# display_driver_rev_A.net
KiCad netlist of a schematic drawn in EAGLE
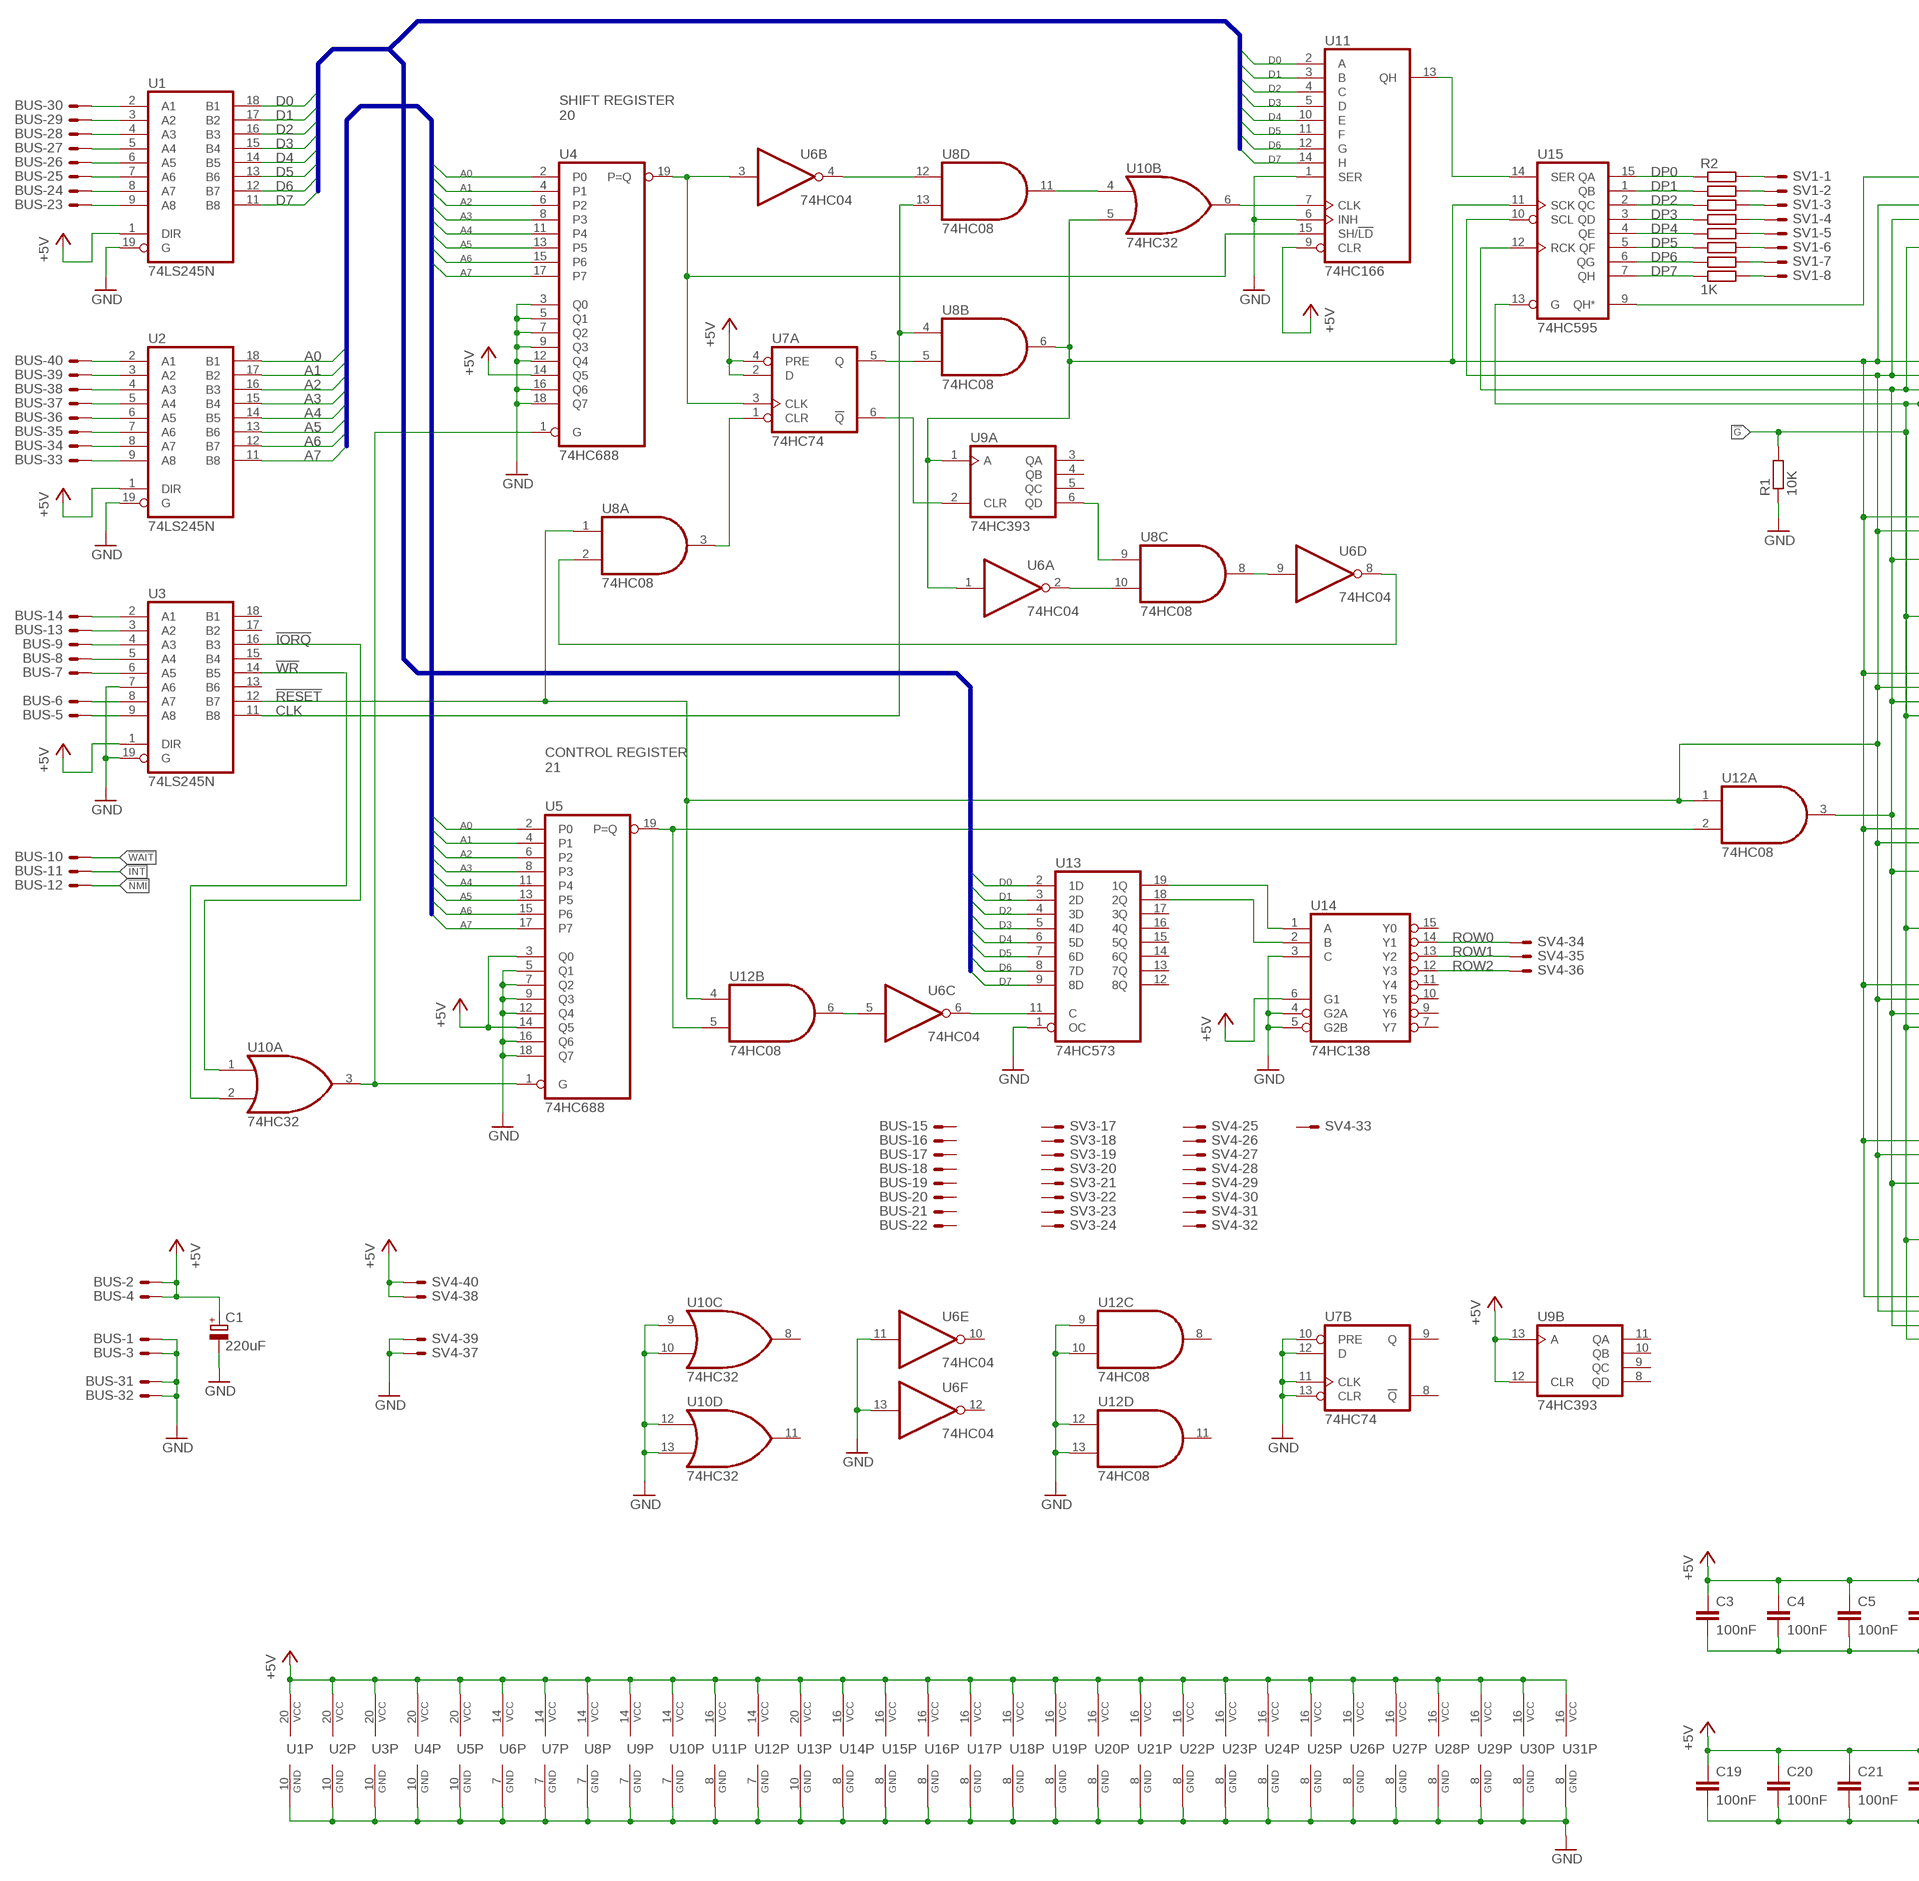
[diagram p0: schematic, sheet 1, part 1 of 2]
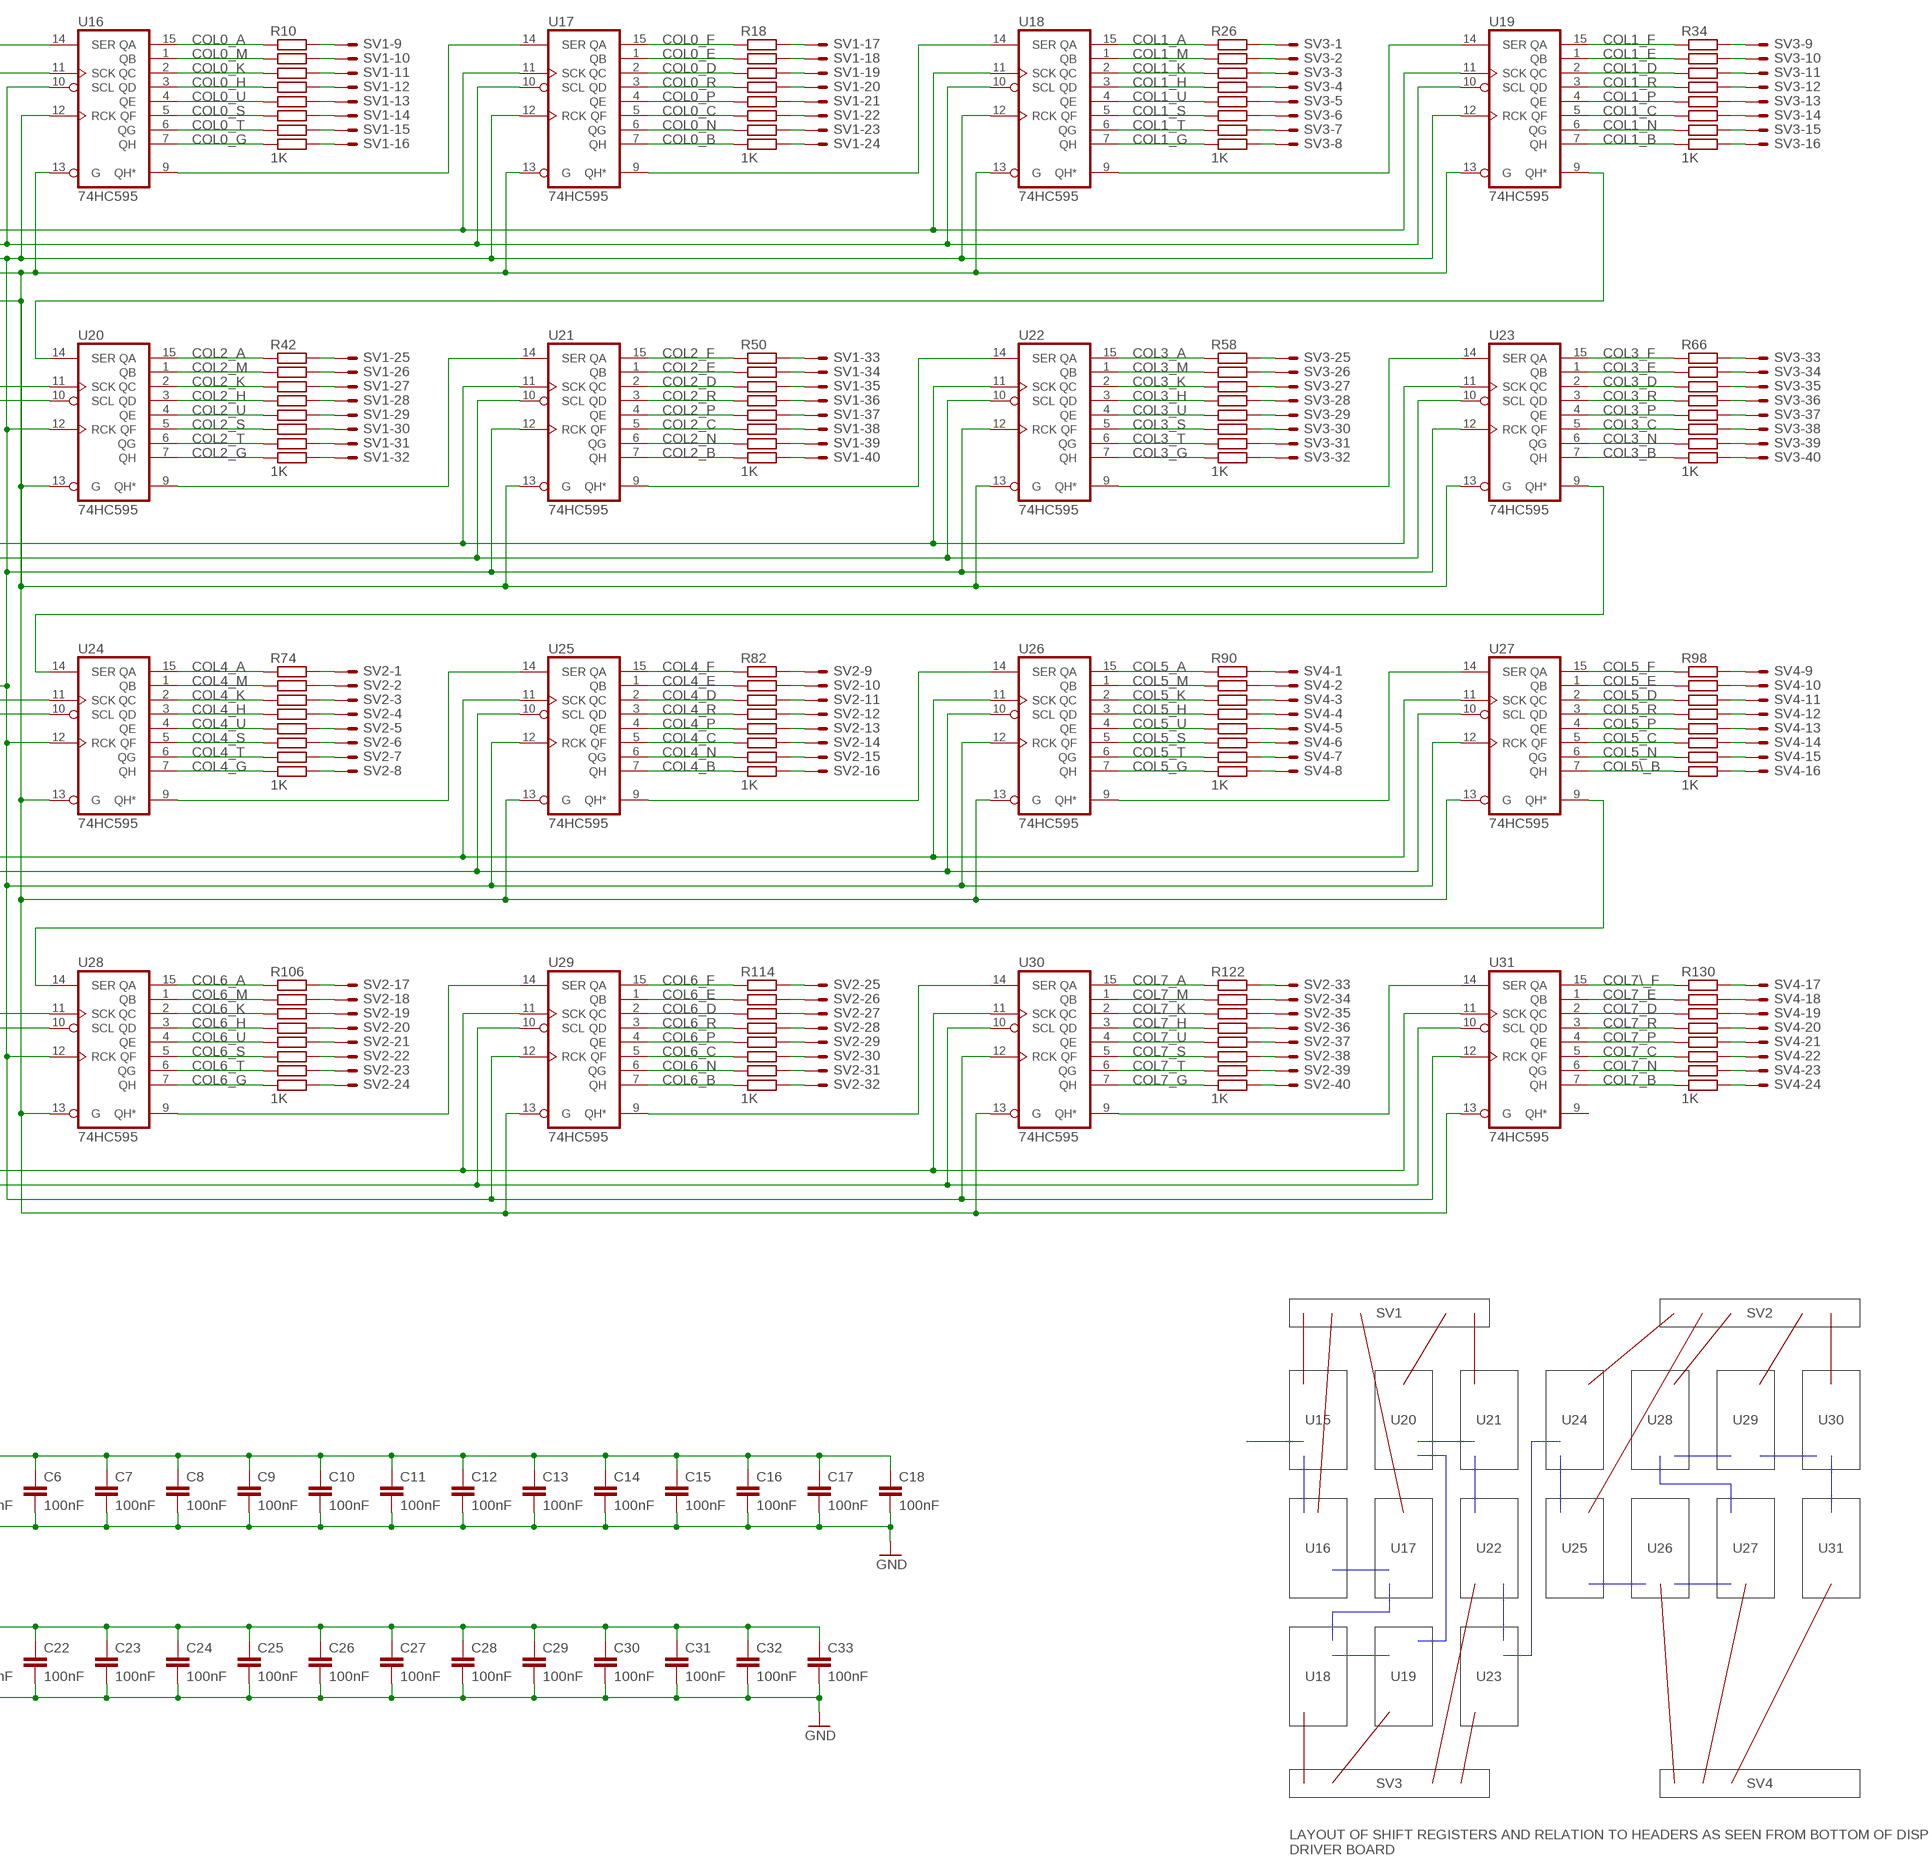
[diagram p1: schematic, sheet 1, part 2 of 2]

(export (version "E")
  (design (tool "Eeschema 10.0.6"))
  (components
    (comp (ref "BUS")
      (value "ML40E")
      (footprint "eagle-import:ML40")
      (libsource (lib "eagle-import") (part "ML40E"))
    )
    (comp (ref "C1")
      (value "220uF")
      (footprint "eagle-import:E3,5-8")
      (libsource (lib "eagle-import") (part "CPOL-EUE3.5-8"))
    )
    (comp (ref "C3")
      (value "100nF")
      (footprint "eagle-import:C050-025X075")
      (libsource (lib "eagle-import") (part "C-EU050-025X075"))
    )
    (comp (ref "C4")
      (value "100nF")
      (footprint "eagle-import:C050-025X075")
      (libsource (lib "eagle-import") (part "C-EU050-025X075"))
    )
    (comp (ref "C5")
      (value "100nF")
      (footprint "eagle-import:C050-025X075")
      (libsource (lib "eagle-import") (part "C-EU050-025X075"))
    )
    (comp (ref "C6")
      (value "100nF")
      (footprint "eagle-import:C050-025X075")
      (libsource (lib "eagle-import") (part "C-EU050-025X075"))
    )
    (comp (ref "C7")
      (value "100nF")
      (footprint "eagle-import:C050-025X075")
      (libsource (lib "eagle-import") (part "C-EU050-025X075"))
    )
    (comp (ref "C8")
      (value "100nF")
      (footprint "eagle-import:C050-025X075")
      (libsource (lib "eagle-import") (part "C-EU050-025X075"))
    )
    (comp (ref "C9")
      (value "100nF")
      (footprint "eagle-import:C050-025X075")
      (libsource (lib "eagle-import") (part "C-EU050-025X075"))
    )
    (comp (ref "C10")
      (value "100nF")
      (footprint "eagle-import:C050-025X075")
      (libsource (lib "eagle-import") (part "C-EU050-025X075"))
    )
    (comp (ref "C11")
      (value "100nF")
      (footprint "eagle-import:C050-025X075")
      (libsource (lib "eagle-import") (part "C-EU050-025X075"))
    )
    (comp (ref "C12")
      (value "100nF")
      (footprint "eagle-import:C050-025X075")
      (libsource (lib "eagle-import") (part "C-EU050-025X075"))
    )
    (comp (ref "C13")
      (value "100nF")
      (footprint "eagle-import:C050-025X075")
      (libsource (lib "eagle-import") (part "C-EU050-025X075"))
    )
    (comp (ref "C14")
      (value "100nF")
      (footprint "eagle-import:C050-025X075")
      (libsource (lib "eagle-import") (part "C-EU050-025X075"))
    )
    (comp (ref "C15")
      (value "100nF")
      (footprint "eagle-import:C050-025X075")
      (libsource (lib "eagle-import") (part "C-EU050-025X075"))
    )
    (comp (ref "C16")
      (value "100nF")
      (footprint "eagle-import:C050-025X075")
      (libsource (lib "eagle-import") (part "C-EU050-025X075"))
    )
    (comp (ref "C17")
      (value "100nF")
      (footprint "eagle-import:C050-025X075")
      (libsource (lib "eagle-import") (part "C-EU050-025X075"))
    )
    (comp (ref "C18")
      (value "100nF")
      (footprint "eagle-import:C050-025X075")
      (libsource (lib "eagle-import") (part "C-EU050-025X075"))
    )
    (comp (ref "C19")
      (value "100nF")
      (footprint "eagle-import:C050-025X075")
      (libsource (lib "eagle-import") (part "C-EU050-025X075"))
    )
    (comp (ref "C20")
      (value "100nF")
      (footprint "eagle-import:C050-025X075")
      (libsource (lib "eagle-import") (part "C-EU050-025X075"))
    )
    (comp (ref "C21")
      (value "100nF")
      (footprint "eagle-import:C050-025X075")
      (libsource (lib "eagle-import") (part "C-EU050-025X075"))
    )
    (comp (ref "C22")
      (value "100nF")
      (footprint "eagle-import:C050-025X075")
      (libsource (lib "eagle-import") (part "C-EU050-025X075"))
    )
    (comp (ref "C23")
      (value "100nF")
      (footprint "eagle-import:C050-025X075")
      (libsource (lib "eagle-import") (part "C-EU050-025X075"))
    )
    (comp (ref "C24")
      (value "100nF")
      (footprint "eagle-import:C050-025X075")
      (libsource (lib "eagle-import") (part "C-EU050-025X075"))
    )
    (comp (ref "C25")
      (value "100nF")
      (footprint "eagle-import:C050-025X075")
      (libsource (lib "eagle-import") (part "C-EU050-025X075"))
    )
    (comp (ref "C26")
      (value "100nF")
      (footprint "eagle-import:C050-025X075")
      (libsource (lib "eagle-import") (part "C-EU050-025X075"))
    )
    (comp (ref "C27")
      (value "100nF")
      (footprint "eagle-import:C050-025X075")
      (libsource (lib "eagle-import") (part "C-EU050-025X075"))
    )
    (comp (ref "C28")
      (value "100nF")
      (footprint "eagle-import:C050-025X075")
      (libsource (lib "eagle-import") (part "C-EU050-025X075"))
    )
    (comp (ref "C29")
      (value "100nF")
      (footprint "eagle-import:C050-025X075")
      (libsource (lib "eagle-import") (part "C-EU050-025X075"))
    )
    (comp (ref "C30")
      (value "100nF")
      (footprint "eagle-import:C050-025X075")
      (libsource (lib "eagle-import") (part "C-EU050-025X075"))
    )
    (comp (ref "C31")
      (value "100nF")
      (footprint "eagle-import:C050-025X075")
      (libsource (lib "eagle-import") (part "C-EU050-025X075"))
    )
    (comp (ref "C32")
      (value "100nF")
      (footprint "eagle-import:C050-025X075")
      (libsource (lib "eagle-import") (part "C-EU050-025X075"))
    )
    (comp (ref "C33")
      (value "100nF")
      (footprint "eagle-import:C050-025X075")
      (libsource (lib "eagle-import") (part "C-EU050-025X075"))
    )
    (comp (ref "R1")
      (value "10K")
      (footprint "eagle-import:0207_10")
      (libsource (lib "eagle-import") (part "R-EU_0207/10"))
    )
    (comp (ref "R2")
      (value "1K")
      (footprint "eagle-import:0207_10")
      (libsource (lib "eagle-import") (part "R-EU_0207/10"))
    )
    (comp (ref "R3")
      (value "1K")
      (footprint "eagle-import:0207_10")
      (libsource (lib "eagle-import") (part "R-EU_0207/10"))
    )
    (comp (ref "R4")
      (value "1K")
      (footprint "eagle-import:0207_10")
      (libsource (lib "eagle-import") (part "R-EU_0207/10"))
    )
    (comp (ref "R5")
      (value "1K")
      (footprint "eagle-import:0207_10")
      (libsource (lib "eagle-import") (part "R-EU_0207/10"))
    )
    (comp (ref "R6")
      (value "1K")
      (footprint "eagle-import:0207_10")
      (libsource (lib "eagle-import") (part "R-EU_0207/10"))
    )
    (comp (ref "R7")
      (value "1K")
      (footprint "eagle-import:0207_10")
      (libsource (lib "eagle-import") (part "R-EU_0207/10"))
    )
    (comp (ref "R8")
      (value "1K")
      (footprint "eagle-import:0207_10")
      (libsource (lib "eagle-import") (part "R-EU_0207/10"))
    )
    (comp (ref "R9")
      (value "1K")
      (footprint "eagle-import:0207_10")
      (libsource (lib "eagle-import") (part "R-EU_0207/10"))
    )
    (comp (ref "R10")
      (value "1K")
      (footprint "eagle-import:0207_10")
      (libsource (lib "eagle-import") (part "R-EU_0207/10"))
    )
    (comp (ref "R11")
      (value "1K")
      (footprint "eagle-import:0207_10")
      (libsource (lib "eagle-import") (part "R-EU_0207/10"))
    )
    (comp (ref "R12")
      (value "1K")
      (footprint "eagle-import:0207_10")
      (libsource (lib "eagle-import") (part "R-EU_0207/10"))
    )
    (comp (ref "R13")
      (value "1K")
      (footprint "eagle-import:0207_10")
      (libsource (lib "eagle-import") (part "R-EU_0207/10"))
    )
    (comp (ref "R14")
      (value "1K")
      (footprint "eagle-import:0207_10")
      (libsource (lib "eagle-import") (part "R-EU_0207/10"))
    )
    (comp (ref "R15")
      (value "1K")
      (footprint "eagle-import:0207_10")
      (libsource (lib "eagle-import") (part "R-EU_0207/10"))
    )
    (comp (ref "R16")
      (value "1K")
      (footprint "eagle-import:0207_10")
      (libsource (lib "eagle-import") (part "R-EU_0207/10"))
    )
    (comp (ref "R17")
      (value "1K")
      (footprint "eagle-import:0207_10")
      (libsource (lib "eagle-import") (part "R-EU_0207/10"))
    )
    (comp (ref "R18")
      (value "1K")
      (footprint "eagle-import:0207_10")
      (libsource (lib "eagle-import") (part "R-EU_0207/10"))
    )
    (comp (ref "R19")
      (value "1K")
      (footprint "eagle-import:0207_10")
      (libsource (lib "eagle-import") (part "R-EU_0207/10"))
    )
    (comp (ref "R20")
      (value "1K")
      (footprint "eagle-import:0207_10")
      (libsource (lib "eagle-import") (part "R-EU_0207/10"))
    )
    (comp (ref "R21")
      (value "1K")
      (footprint "eagle-import:0207_10")
      (libsource (lib "eagle-import") (part "R-EU_0207/10"))
    )
    (comp (ref "R22")
      (value "1K")
      (footprint "eagle-import:0207_10")
      (libsource (lib "eagle-import") (part "R-EU_0207/10"))
    )
    (comp (ref "R23")
      (value "1K")
      (footprint "eagle-import:0207_10")
      (libsource (lib "eagle-import") (part "R-EU_0207/10"))
    )
    (comp (ref "R24")
      (value "1K")
      (footprint "eagle-import:0207_10")
      (libsource (lib "eagle-import") (part "R-EU_0207/10"))
    )
    (comp (ref "R25")
      (value "1K")
      (footprint "eagle-import:0207_10")
      (libsource (lib "eagle-import") (part "R-EU_0207/10"))
    )
    (comp (ref "R26")
      (value "1K")
      (footprint "eagle-import:0207_10")
      (libsource (lib "eagle-import") (part "R-EU_0207/10"))
    )
    (comp (ref "R27")
      (value "1K")
      (footprint "eagle-import:0207_10")
      (libsource (lib "eagle-import") (part "R-EU_0207/10"))
    )
    (comp (ref "R28")
      (value "1K")
      (footprint "eagle-import:0207_10")
      (libsource (lib "eagle-import") (part "R-EU_0207/10"))
    )
    (comp (ref "R29")
      (value "1K")
      (footprint "eagle-import:0207_10")
      (libsource (lib "eagle-import") (part "R-EU_0207/10"))
    )
    (comp (ref "R30")
      (value "1K")
      (footprint "eagle-import:0207_10")
      (libsource (lib "eagle-import") (part "R-EU_0207/10"))
    )
    (comp (ref "R31")
      (value "1K")
      (footprint "eagle-import:0207_10")
      (libsource (lib "eagle-import") (part "R-EU_0207/10"))
    )
    (comp (ref "R32")
      (value "1K")
      (footprint "eagle-import:0207_10")
      (libsource (lib "eagle-import") (part "R-EU_0207/10"))
    )
    (comp (ref "R33")
      (value "1K")
      (footprint "eagle-import:0207_10")
      (libsource (lib "eagle-import") (part "R-EU_0207/10"))
    )
    (comp (ref "R34")
      (value "1K")
      (footprint "eagle-import:0207_10")
      (libsource (lib "eagle-import") (part "R-EU_0207/10"))
    )
    (comp (ref "R35")
      (value "1K")
      (footprint "eagle-import:0207_10")
      (libsource (lib "eagle-import") (part "R-EU_0207/10"))
    )
    (comp (ref "R36")
      (value "1K")
      (footprint "eagle-import:0207_10")
      (libsource (lib "eagle-import") (part "R-EU_0207/10"))
    )
    (comp (ref "R37")
      (value "1K")
      (footprint "eagle-import:0207_10")
      (libsource (lib "eagle-import") (part "R-EU_0207/10"))
    )
    (comp (ref "R38")
      (value "1K")
      (footprint "eagle-import:0207_10")
      (libsource (lib "eagle-import") (part "R-EU_0207/10"))
    )
    (comp (ref "R39")
      (value "1K")
      (footprint "eagle-import:0207_10")
      (libsource (lib "eagle-import") (part "R-EU_0207/10"))
    )
    (comp (ref "R40")
      (value "1K")
      (footprint "eagle-import:0207_10")
      (libsource (lib "eagle-import") (part "R-EU_0207/10"))
    )
    (comp (ref "R41")
      (value "1K")
      (footprint "eagle-import:0207_10")
      (libsource (lib "eagle-import") (part "R-EU_0207/10"))
    )
    (comp (ref "R42")
      (value "1K")
      (footprint "eagle-import:0207_10")
      (libsource (lib "eagle-import") (part "R-EU_0207/10"))
    )
    (comp (ref "R43")
      (value "1K")
      (footprint "eagle-import:0207_10")
      (libsource (lib "eagle-import") (part "R-EU_0207/10"))
    )
    (comp (ref "R44")
      (value "1K")
      (footprint "eagle-import:0207_10")
      (libsource (lib "eagle-import") (part "R-EU_0207/10"))
    )
    (comp (ref "R45")
      (value "1K")
      (footprint "eagle-import:0207_10")
      (libsource (lib "eagle-import") (part "R-EU_0207/10"))
    )
    (comp (ref "R46")
      (value "1K")
      (footprint "eagle-import:0207_10")
      (libsource (lib "eagle-import") (part "R-EU_0207/10"))
    )
    (comp (ref "R47")
      (value "1K")
      (footprint "eagle-import:0207_10")
      (libsource (lib "eagle-import") (part "R-EU_0207/10"))
    )
    (comp (ref "R48")
      (value "1K")
      (footprint "eagle-import:0207_10")
      (libsource (lib "eagle-import") (part "R-EU_0207/10"))
    )
    (comp (ref "R49")
      (value "1K")
      (footprint "eagle-import:0207_10")
      (libsource (lib "eagle-import") (part "R-EU_0207/10"))
    )
    (comp (ref "R50")
      (value "1K")
      (footprint "eagle-import:0207_10")
      (libsource (lib "eagle-import") (part "R-EU_0207/10"))
    )
    (comp (ref "R51")
      (value "1K")
      (footprint "eagle-import:0207_10")
      (libsource (lib "eagle-import") (part "R-EU_0207/10"))
    )
    (comp (ref "R52")
      (value "1K")
      (footprint "eagle-import:0207_10")
      (libsource (lib "eagle-import") (part "R-EU_0207/10"))
    )
    (comp (ref "R53")
      (value "1K")
      (footprint "eagle-import:0207_10")
      (libsource (lib "eagle-import") (part "R-EU_0207/10"))
    )
    (comp (ref "R54")
      (value "1K")
      (footprint "eagle-import:0207_10")
      (libsource (lib "eagle-import") (part "R-EU_0207/10"))
    )
    (comp (ref "R55")
      (value "1K")
      (footprint "eagle-import:0207_10")
      (libsource (lib "eagle-import") (part "R-EU_0207/10"))
    )
    (comp (ref "R56")
      (value "1K")
      (footprint "eagle-import:0207_10")
      (libsource (lib "eagle-import") (part "R-EU_0207/10"))
    )
    (comp (ref "R57")
      (value "1K")
      (footprint "eagle-import:0207_10")
      (libsource (lib "eagle-import") (part "R-EU_0207/10"))
    )
    (comp (ref "R58")
      (value "1K")
      (footprint "eagle-import:0207_10")
      (libsource (lib "eagle-import") (part "R-EU_0207/10"))
    )
    (comp (ref "R59")
      (value "1K")
      (footprint "eagle-import:0207_10")
      (libsource (lib "eagle-import") (part "R-EU_0207/10"))
    )
    (comp (ref "R60")
      (value "1K")
      (footprint "eagle-import:0207_10")
      (libsource (lib "eagle-import") (part "R-EU_0207/10"))
    )
    (comp (ref "R61")
      (value "1K")
      (footprint "eagle-import:0207_10")
      (libsource (lib "eagle-import") (part "R-EU_0207/10"))
    )
    (comp (ref "R62")
      (value "1K")
      (footprint "eagle-import:0207_10")
      (libsource (lib "eagle-import") (part "R-EU_0207/10"))
    )
    (comp (ref "R63")
      (value "1K")
      (footprint "eagle-import:0207_10")
      (libsource (lib "eagle-import") (part "R-EU_0207/10"))
    )
    (comp (ref "R64")
      (value "1K")
      (footprint "eagle-import:0207_10")
      (libsource (lib "eagle-import") (part "R-EU_0207/10"))
    )
    (comp (ref "R65")
      (value "1K")
      (footprint "eagle-import:0207_10")
      (libsource (lib "eagle-import") (part "R-EU_0207/10"))
    )
    (comp (ref "R66")
      (value "1K")
      (footprint "eagle-import:0207_10")
      (libsource (lib "eagle-import") (part "R-EU_0207/10"))
    )
    (comp (ref "R67")
      (value "1K")
      (footprint "eagle-import:0207_10")
      (libsource (lib "eagle-import") (part "R-EU_0207/10"))
    )
    (comp (ref "R68")
      (value "1K")
      (footprint "eagle-import:0207_10")
      (libsource (lib "eagle-import") (part "R-EU_0207/10"))
    )
    (comp (ref "R69")
      (value "1K")
      (footprint "eagle-import:0207_10")
      (libsource (lib "eagle-import") (part "R-EU_0207/10"))
    )
    (comp (ref "R70")
      (value "1K")
      (footprint "eagle-import:0207_10")
      (libsource (lib "eagle-import") (part "R-EU_0207/10"))
    )
    (comp (ref "R71")
      (value "1K")
      (footprint "eagle-import:0207_10")
      (libsource (lib "eagle-import") (part "R-EU_0207/10"))
    )
    (comp (ref "R72")
      (value "1K")
      (footprint "eagle-import:0207_10")
      (libsource (lib "eagle-import") (part "R-EU_0207/10"))
    )
    (comp (ref "R73")
      (value "1K")
      (footprint "eagle-import:0207_10")
      (libsource (lib "eagle-import") (part "R-EU_0207/10"))
    )
    (comp (ref "R74")
      (value "1K")
      (footprint "eagle-import:0207_10")
      (libsource (lib "eagle-import") (part "R-EU_0207/10"))
    )
    (comp (ref "R75")
      (value "1K")
      (footprint "eagle-import:0207_10")
      (libsource (lib "eagle-import") (part "R-EU_0207/10"))
    )
    (comp (ref "R76")
      (value "1K")
      (footprint "eagle-import:0207_10")
      (libsource (lib "eagle-import") (part "R-EU_0207/10"))
    )
    (comp (ref "R77")
      (value "1K")
      (footprint "eagle-import:0207_10")
      (libsource (lib "eagle-import") (part "R-EU_0207/10"))
    )
    (comp (ref "R78")
      (value "1K")
      (footprint "eagle-import:0207_10")
      (libsource (lib "eagle-import") (part "R-EU_0207/10"))
    )
    (comp (ref "R79")
      (value "1K")
      (footprint "eagle-import:0207_10")
      (libsource (lib "eagle-import") (part "R-EU_0207/10"))
    )
    (comp (ref "R80")
      (value "1K")
      (footprint "eagle-import:0207_10")
      (libsource (lib "eagle-import") (part "R-EU_0207/10"))
    )
    (comp (ref "R81")
      (value "1K")
      (footprint "eagle-import:0207_10")
      (libsource (lib "eagle-import") (part "R-EU_0207/10"))
    )
    (comp (ref "R82")
      (value "1K")
      (footprint "eagle-import:0207_10")
      (libsource (lib "eagle-import") (part "R-EU_0207/10"))
    )
    (comp (ref "R83")
      (value "1K")
      (footprint "eagle-import:0207_10")
      (libsource (lib "eagle-import") (part "R-EU_0207/10"))
    )
    (comp (ref "R84")
      (value "1K")
      (footprint "eagle-import:0207_10")
      (libsource (lib "eagle-import") (part "R-EU_0207/10"))
    )
    (comp (ref "R85")
      (value "1K")
      (footprint "eagle-import:0207_10")
      (libsource (lib "eagle-import") (part "R-EU_0207/10"))
    )
    (comp (ref "R86")
      (value "1K")
      (footprint "eagle-import:0207_10")
      (libsource (lib "eagle-import") (part "R-EU_0207/10"))
    )
    (comp (ref "R87")
      (value "1K")
      (footprint "eagle-import:0207_10")
      (libsource (lib "eagle-import") (part "R-EU_0207/10"))
    )
    (comp (ref "R88")
      (value "1K")
      (footprint "eagle-import:0207_10")
      (libsource (lib "eagle-import") (part "R-EU_0207/10"))
    )
    (comp (ref "R89")
      (value "1K")
      (footprint "eagle-import:0207_10")
      (libsource (lib "eagle-import") (part "R-EU_0207/10"))
    )
    (comp (ref "R90")
      (value "1K")
      (footprint "eagle-import:0207_10")
      (libsource (lib "eagle-import") (part "R-EU_0207/10"))
    )
    (comp (ref "R91")
      (value "1K")
      (footprint "eagle-import:0207_10")
      (libsource (lib "eagle-import") (part "R-EU_0207/10"))
    )
    (comp (ref "R92")
      (value "1K")
      (footprint "eagle-import:0207_10")
      (libsource (lib "eagle-import") (part "R-EU_0207/10"))
    )
    (comp (ref "R93")
      (value "1K")
      (footprint "eagle-import:0207_10")
      (libsource (lib "eagle-import") (part "R-EU_0207/10"))
    )
    (comp (ref "R94")
      (value "1K")
      (footprint "eagle-import:0207_10")
      (libsource (lib "eagle-import") (part "R-EU_0207/10"))
    )
    (comp (ref "R95")
      (value "1K")
      (footprint "eagle-import:0207_10")
      (libsource (lib "eagle-import") (part "R-EU_0207/10"))
    )
    (comp (ref "R96")
      (value "1K")
      (footprint "eagle-import:0207_10")
      (libsource (lib "eagle-import") (part "R-EU_0207/10"))
    )
    (comp (ref "R97")
      (value "1K")
      (footprint "eagle-import:0207_10")
      (libsource (lib "eagle-import") (part "R-EU_0207/10"))
    )
    (comp (ref "R98")
      (value "1K")
      (footprint "eagle-import:0207_10")
      (libsource (lib "eagle-import") (part "R-EU_0207/10"))
    )
    (comp (ref "R99")
      (value "1K")
      (footprint "eagle-import:0207_10")
      (libsource (lib "eagle-import") (part "R-EU_0207/10"))
    )
    (comp (ref "R100")
      (value "1K")
      (footprint "eagle-import:0207_10")
      (libsource (lib "eagle-import") (part "R-EU_0207/10"))
    )
    (comp (ref "R101")
      (value "1K")
      (footprint "eagle-import:0207_10")
      (libsource (lib "eagle-import") (part "R-EU_0207/10"))
    )
    (comp (ref "R102")
      (value "1K")
      (footprint "eagle-import:0207_10")
      (libsource (lib "eagle-import") (part "R-EU_0207/10"))
    )
    (comp (ref "R103")
      (value "1K")
      (footprint "eagle-import:0207_10")
      (libsource (lib "eagle-import") (part "R-EU_0207/10"))
    )
    (comp (ref "R104")
      (value "1K")
      (footprint "eagle-import:0207_10")
      (libsource (lib "eagle-import") (part "R-EU_0207/10"))
    )
    (comp (ref "R105")
      (value "1K")
      (footprint "eagle-import:0207_10")
      (libsource (lib "eagle-import") (part "R-EU_0207/10"))
    )
    (comp (ref "R106")
      (value "1K")
      (footprint "eagle-import:0207_10")
      (libsource (lib "eagle-import") (part "R-EU_0207/10"))
    )
    (comp (ref "R107")
      (value "1K")
      (footprint "eagle-import:0207_10")
      (libsource (lib "eagle-import") (part "R-EU_0207/10"))
    )
    (comp (ref "R108")
      (value "1K")
      (footprint "eagle-import:0207_10")
      (libsource (lib "eagle-import") (part "R-EU_0207/10"))
    )
    (comp (ref "R109")
      (value "1K")
      (footprint "eagle-import:0207_10")
      (libsource (lib "eagle-import") (part "R-EU_0207/10"))
    )
    (comp (ref "R110")
      (value "1K")
      (footprint "eagle-import:0207_10")
      (libsource (lib "eagle-import") (part "R-EU_0207/10"))
    )
    (comp (ref "R111")
      (value "1K")
      (footprint "eagle-import:0207_10")
      (libsource (lib "eagle-import") (part "R-EU_0207/10"))
    )
    (comp (ref "R112")
      (value "1K")
      (footprint "eagle-import:0207_10")
      (libsource (lib "eagle-import") (part "R-EU_0207/10"))
    )
    (comp (ref "R113")
      (value "1K")
      (footprint "eagle-import:0207_10")
      (libsource (lib "eagle-import") (part "R-EU_0207/10"))
    )
    (comp (ref "R114")
      (value "1K")
      (footprint "eagle-import:0207_10")
      (libsource (lib "eagle-import") (part "R-EU_0207/10"))
    )
    (comp (ref "R115")
      (value "1K")
      (footprint "eagle-import:0207_10")
      (libsource (lib "eagle-import") (part "R-EU_0207/10"))
    )
    (comp (ref "R116")
      (value "1K")
      (footprint "eagle-import:0207_10")
      (libsource (lib "eagle-import") (part "R-EU_0207/10"))
    )
    (comp (ref "R117")
      (value "1K")
      (footprint "eagle-import:0207_10")
      (libsource (lib "eagle-import") (part "R-EU_0207/10"))
    )
    (comp (ref "R118")
      (value "1K")
      (footprint "eagle-import:0207_10")
      (libsource (lib "eagle-import") (part "R-EU_0207/10"))
    )
    (comp (ref "R119")
      (value "1K")
      (footprint "eagle-import:0207_10")
      (libsource (lib "eagle-import") (part "R-EU_0207/10"))
    )
    (comp (ref "R120")
      (value "1K")
      (footprint "eagle-import:0207_10")
      (libsource (lib "eagle-import") (part "R-EU_0207/10"))
    )
    (comp (ref "R121")
      (value "1K")
      (footprint "eagle-import:0207_10")
      (libsource (lib "eagle-import") (part "R-EU_0207/10"))
    )
    (comp (ref "R122")
      (value "1K")
      (footprint "eagle-import:0207_10")
      (libsource (lib "eagle-import") (part "R-EU_0207/10"))
    )
    (comp (ref "R123")
      (value "1K")
      (footprint "eagle-import:0207_10")
      (libsource (lib "eagle-import") (part "R-EU_0207/10"))
    )
    (comp (ref "R124")
      (value "1K")
      (footprint "eagle-import:0207_10")
      (libsource (lib "eagle-import") (part "R-EU_0207/10"))
    )
    (comp (ref "R125")
      (value "1K")
      (footprint "eagle-import:0207_10")
      (libsource (lib "eagle-import") (part "R-EU_0207/10"))
    )
    (comp (ref "R126")
      (value "1K")
      (footprint "eagle-import:0207_10")
      (libsource (lib "eagle-import") (part "R-EU_0207/10"))
    )
    (comp (ref "R127")
      (value "1K")
      (footprint "eagle-import:0207_10")
      (libsource (lib "eagle-import") (part "R-EU_0207/10"))
    )
    (comp (ref "R128")
      (value "1K")
      (footprint "eagle-import:0207_10")
      (libsource (lib "eagle-import") (part "R-EU_0207/10"))
    )
    (comp (ref "R129")
      (value "1K")
      (footprint "eagle-import:0207_10")
      (libsource (lib "eagle-import") (part "R-EU_0207/10"))
    )
    (comp (ref "R130")
      (value "1K")
      (footprint "eagle-import:0207_10")
      (libsource (lib "eagle-import") (part "R-EU_0207/10"))
    )
    (comp (ref "R131")
      (value "1K")
      (footprint "eagle-import:0207_10")
      (libsource (lib "eagle-import") (part "R-EU_0207/10"))
    )
    (comp (ref "R132")
      (value "1K")
      (footprint "eagle-import:0207_10")
      (libsource (lib "eagle-import") (part "R-EU_0207/10"))
    )
    (comp (ref "R133")
      (value "1K")
      (footprint "eagle-import:0207_10")
      (libsource (lib "eagle-import") (part "R-EU_0207/10"))
    )
    (comp (ref "R134")
      (value "1K")
      (footprint "eagle-import:0207_10")
      (libsource (lib "eagle-import") (part "R-EU_0207/10"))
    )
    (comp (ref "R135")
      (value "1K")
      (footprint "eagle-import:0207_10")
      (libsource (lib "eagle-import") (part "R-EU_0207/10"))
    )
    (comp (ref "R136")
      (value "1K")
      (footprint "eagle-import:0207_10")
      (libsource (lib "eagle-import") (part "R-EU_0207/10"))
    )
    (comp (ref "R137")
      (value "1K")
      (footprint "eagle-import:0207_10")
      (libsource (lib "eagle-import") (part "R-EU_0207/10"))
    )
    (comp (ref "SV1")
      (value "ML40E")
      (footprint "eagle-import:ML40")
      (libsource (lib "eagle-import") (part "ML40E"))
    )
    (comp (ref "SV2")
      (value "ML40E")
      (footprint "eagle-import:ML40")
      (libsource (lib "eagle-import") (part "ML40E"))
    )
    (comp (ref "SV3")
      (value "ML40E")
      (footprint "eagle-import:ML40")
      (libsource (lib "eagle-import") (part "ML40E"))
    )
    (comp (ref "SV4")
      (value "ML40E")
      (footprint "eagle-import:ML40")
      (libsource (lib "eagle-import") (part "ML40E"))
    )
    (comp (ref "U1")
      (value "74LS245N")
      (footprint "eagle-import:DIL20")
      (libsource (lib "eagle-import") (part "74245NLS"))
    )
    (comp (ref "U2")
      (value "74LS245N")
      (footprint "eagle-import:DIL20")
      (libsource (lib "eagle-import") (part "74245NLS"))
    )
    (comp (ref "U3")
      (value "74LS245N")
      (footprint "eagle-import:DIL20")
      (libsource (lib "eagle-import") (part "74245NLS"))
    )
    (comp (ref "U4")
      (value "74HC688")
      (footprint "eagle-import:DIL20")
      (libsource (lib "eagle-import") (part "74688NLS"))
    )
    (comp (ref "U5")
      (value "74HC688")
      (footprint "eagle-import:DIL20")
      (libsource (lib "eagle-import") (part "74688NLS"))
    )
    (comp (ref "U6")
      (value "74HC04")
      (footprint "eagle-import:DIL14")
      (libsource (lib "eagle-import") (part "7404NLS"))
    )
    (comp (ref "U7")
      (value "74HC74")
      (footprint "eagle-import:DIL14")
      (libsource (lib "eagle-import") (part "7474NLS"))
    )
    (comp (ref "U8")
      (value "74HC08")
      (footprint "eagle-import:DIL14")
      (libsource (lib "eagle-import") (part "7408NLS"))
    )
    (comp (ref "U9")
      (value "74HC393")
      (footprint "eagle-import:DIL14")
      (libsource (lib "eagle-import") (part "74393NLS"))
    )
    (comp (ref "U10")
      (value "74HC32")
      (footprint "eagle-import:DIL14")
      (libsource (lib "eagle-import") (part "7432NLS"))
    )
    (comp (ref "U11")
      (value "74HC166")
      (footprint "eagle-import:DIL16")
      (libsource (lib "eagle-import") (part "74166NLS"))
    )
    (comp (ref "U12")
      (value "74HC08")
      (footprint "eagle-import:DIL14")
      (fields (field (name "SPICEPREFIX") "J"))
      (libsource (lib "eagle-import") (part "7408NLS"))
    )
    (comp (ref "U13")
      (value "74HC573")
      (footprint "eagle-import:DIL20")
      (libsource (lib "eagle-import") (part "74573NHC"))
    )
    (comp (ref "U14")
      (value "74HC138")
      (footprint "eagle-import:DIL16")
      (libsource (lib "eagle-import") (part "74138NLS"))
    )
    (comp (ref "U15")
      (value "74HC595")
      (footprint "eagle-import:DIL16")
      (libsource (lib "eagle-import") (part "74595NLS"))
    )
    (comp (ref "U16")
      (value "74HC595")
      (footprint "eagle-import:DIL16")
      (libsource (lib "eagle-import") (part "74595NLS"))
    )
    (comp (ref "U17")
      (value "74HC595")
      (footprint "eagle-import:DIL16")
      (libsource (lib "eagle-import") (part "74595NLS"))
    )
    (comp (ref "U18")
      (value "74HC595")
      (footprint "eagle-import:DIL16")
      (libsource (lib "eagle-import") (part "74595NLS"))
    )
    (comp (ref "U19")
      (value "74HC595")
      (footprint "eagle-import:DIL16")
      (libsource (lib "eagle-import") (part "74595NLS"))
    )
    (comp (ref "U20")
      (value "74HC595")
      (footprint "eagle-import:DIL16")
      (libsource (lib "eagle-import") (part "74595NLS"))
    )
    (comp (ref "U21")
      (value "74HC595")
      (footprint "eagle-import:DIL16")
      (libsource (lib "eagle-import") (part "74595NLS"))
    )
    (comp (ref "U22")
      (value "74HC595")
      (footprint "eagle-import:DIL16")
      (libsource (lib "eagle-import") (part "74595NLS"))
    )
    (comp (ref "U23")
      (value "74HC595")
      (footprint "eagle-import:DIL16")
      (libsource (lib "eagle-import") (part "74595NLS"))
    )
    (comp (ref "U24")
      (value "74HC595")
      (footprint "eagle-import:DIL16")
      (libsource (lib "eagle-import") (part "74595NLS"))
    )
    (comp (ref "U25")
      (value "74HC595")
      (footprint "eagle-import:DIL16")
      (libsource (lib "eagle-import") (part "74595NLS"))
    )
    (comp (ref "U26")
      (value "74HC595")
      (footprint "eagle-import:DIL16")
      (libsource (lib "eagle-import") (part "74595NLS"))
    )
    (comp (ref "U27")
      (value "74HC595")
      (footprint "eagle-import:DIL16")
      (libsource (lib "eagle-import") (part "74595NLS"))
    )
    (comp (ref "U28")
      (value "74HC595")
      (footprint "eagle-import:DIL16")
      (libsource (lib "eagle-import") (part "74595NLS"))
    )
    (comp (ref "U29")
      (value "74HC595")
      (footprint "eagle-import:DIL16")
      (libsource (lib "eagle-import") (part "74595NLS"))
    )
    (comp (ref "U30")
      (value "74HC595")
      (footprint "eagle-import:DIL16")
      (libsource (lib "eagle-import") (part "74595NLS"))
    )
    (comp (ref "U31")
      (value "74HC595")
      (footprint "eagle-import:DIL16")
      (libsource (lib "eagle-import") (part "74595NLS"))
    )
  )
  (nets
    (net (code "1") (name "+5V") (class "Default")
      (node (ref "BUS") (pin "2") (pinfunction "S_2") (pintype "passive"))
      (node (ref "BUS") (pin "4") (pinfunction "S_4") (pintype "passive"))
      (node (ref "C1") (pin "+") (pinfunction "+_+") (pintype "passive"))
      (node (ref "C10") (pin "1") (pinfunction "1_1") (pintype "passive"))
      (node (ref "C11") (pin "1") (pinfunction "1_1") (pintype "passive"))
      (node (ref "C12") (pin "1") (pinfunction "1_1") (pintype "passive"))
      (node (ref "C13") (pin "1") (pinfunction "1_1") (pintype "passive"))
      (node (ref "C14") (pin "1") (pinfunction "1_1") (pintype "passive"))
      (node (ref "C15") (pin "1") (pinfunction "1_1") (pintype "passive"))
      (node (ref "C16") (pin "1") (pinfunction "1_1") (pintype "passive"))
      (node (ref "C17") (pin "1") (pinfunction "1_1") (pintype "passive"))
      (node (ref "C18") (pin "1") (pinfunction "1_1") (pintype "passive"))
      (node (ref "C19") (pin "1") (pinfunction "1_1") (pintype "passive"))
      (node (ref "C20") (pin "1") (pinfunction "1_1") (pintype "passive"))
      (node (ref "C21") (pin "1") (pinfunction "1_1") (pintype "passive"))
      (node (ref "C22") (pin "1") (pinfunction "1_1") (pintype "passive"))
      (node (ref "C23") (pin "1") (pinfunction "1_1") (pintype "passive"))
      (node (ref "C24") (pin "1") (pinfunction "1_1") (pintype "passive"))
      (node (ref "C25") (pin "1") (pinfunction "1_1") (pintype "passive"))
      (node (ref "C26") (pin "1") (pinfunction "1_1") (pintype "passive"))
      (node (ref "C27") (pin "1") (pinfunction "1_1") (pintype "passive"))
      (node (ref "C28") (pin "1") (pinfunction "1_1") (pintype "passive"))
      (node (ref "C29") (pin "1") (pinfunction "1_1") (pintype "passive"))
      (node (ref "C3") (pin "1") (pinfunction "1_1") (pintype "passive"))
      (node (ref "C30") (pin "1") (pinfunction "1_1") (pintype "passive"))
      (node (ref "C31") (pin "1") (pinfunction "1_1") (pintype "passive"))
      (node (ref "C32") (pin "1") (pinfunction "1_1") (pintype "passive"))
      (node (ref "C33") (pin "1") (pinfunction "1_1") (pintype "passive"))
      (node (ref "C4") (pin "1") (pinfunction "1_1") (pintype "passive"))
      (node (ref "C5") (pin "1") (pinfunction "1_1") (pintype "passive"))
      (node (ref "C6") (pin "1") (pinfunction "1_1") (pintype "passive"))
      (node (ref "C7") (pin "1") (pinfunction "1_1") (pintype "passive"))
      (node (ref "C8") (pin "1") (pinfunction "1_1") (pintype "passive"))
      (node (ref "C9") (pin "1") (pinfunction "1_1") (pintype "passive"))
      (node (ref "SV4") (pin "38") (pinfunction "S_38") (pintype "passive"))
      (node (ref "SV4") (pin "40") (pinfunction "S_40") (pintype "passive"))
      (node (ref "U1") (pin "1") (pinfunction "DIR_1") (pintype "input"))
      (node (ref "U1") (pin "20") (pinfunction "VCC_20") (pintype "power_in"))
      (node (ref "U10") (pin "14") (pinfunction "VCC_14") (pintype "power_in"))
      (node (ref "U11") (pin "16") (pinfunction "VCC_16") (pintype "power_in"))
      (node (ref "U11") (pin "9") (pinfunction "CLR_9") (pintype "input"))
      (node (ref "U12") (pin "14") (pinfunction "VCC_14") (pintype "power_in"))
      (node (ref "U13") (pin "20") (pinfunction "VCC_20") (pintype "power_in"))
      (node (ref "U14") (pin "16") (pinfunction "VCC_16") (pintype "power_in"))
      (node (ref "U14") (pin "6") (pinfunction "G1_6") (pintype "input"))
      (node (ref "U15") (pin "16") (pinfunction "VCC_16") (pintype "power_in"))
      (node (ref "U16") (pin "16") (pinfunction "VCC_16") (pintype "power_in"))
      (node (ref "U17") (pin "16") (pinfunction "VCC_16") (pintype "power_in"))
      (node (ref "U18") (pin "16") (pinfunction "VCC_16") (pintype "power_in"))
      (node (ref "U19") (pin "16") (pinfunction "VCC_16") (pintype "power_in"))
      (node (ref "U2") (pin "1") (pinfunction "DIR_1") (pintype "input"))
      (node (ref "U2") (pin "20") (pinfunction "VCC_20") (pintype "power_in"))
      (node (ref "U20") (pin "16") (pinfunction "VCC_16") (pintype "power_in"))
      (node (ref "U21") (pin "16") (pinfunction "VCC_16") (pintype "power_in"))
      (node (ref "U22") (pin "16") (pinfunction "VCC_16") (pintype "power_in"))
      (node (ref "U23") (pin "16") (pinfunction "VCC_16") (pintype "power_in"))
      (node (ref "U24") (pin "16") (pinfunction "VCC_16") (pintype "power_in"))
      (node (ref "U25") (pin "16") (pinfunction "VCC_16") (pintype "power_in"))
      (node (ref "U26") (pin "16") (pinfunction "VCC_16") (pintype "power_in"))
      (node (ref "U27") (pin "16") (pinfunction "VCC_16") (pintype "power_in"))
      (node (ref "U28") (pin "16") (pinfunction "VCC_16") (pintype "power_in"))
      (node (ref "U29") (pin "16") (pinfunction "VCC_16") (pintype "power_in"))
      (node (ref "U3") (pin "1") (pinfunction "DIR_1") (pintype "input"))
      (node (ref "U3") (pin "20") (pinfunction "VCC_20") (pintype "power_in"))
      (node (ref "U30") (pin "16") (pinfunction "VCC_16") (pintype "power_in"))
      (node (ref "U31") (pin "16") (pinfunction "VCC_16") (pintype "power_in"))
      (node (ref "U4") (pin "14") (pinfunction "Q5_14") (pintype "input"))
      (node (ref "U4") (pin "20") (pinfunction "VCC_20") (pintype "power_in"))
      (node (ref "U5") (pin "14") (pinfunction "Q5_14") (pintype "input"))
      (node (ref "U5") (pin "20") (pinfunction "VCC_20") (pintype "power_in"))
      (node (ref "U5") (pin "3") (pinfunction "Q0_3") (pintype "input"))
      (node (ref "U6") (pin "14") (pinfunction "VCC_14") (pintype "power_in"))
      (node (ref "U7") (pin "14") (pinfunction "VCC_14") (pintype "power_in"))
      (node (ref "U7") (pin "2") (pinfunction "D_2") (pintype "input"))
      (node (ref "U7") (pin "4") (pinfunction "PRE_4") (pintype "input"))
      (node (ref "U8") (pin "14") (pinfunction "VCC_14") (pintype "power_in"))
      (node (ref "U9") (pin "12") (pinfunction "CLR_12") (pintype "input"))
      (node (ref "U9") (pin "13") (pinfunction "A_13") (pintype "input"))
      (node (ref "U9") (pin "14") (pinfunction "VCC_14") (pintype "power_in"))
    )
    (net (code "2") (name "/A0") (class "Default")
      (node (ref "U2") (pin "18") (pinfunction "B1_18") (pintype "bidirectional"))
      (node (ref "U4") (pin "2") (pinfunction "P0_2") (pintype "input"))
      (node (ref "U5") (pin "2") (pinfunction "P0_2") (pintype "input"))
    )
    (net (code "3") (name "/A1") (class "Default")
      (node (ref "U2") (pin "17") (pinfunction "B2_17") (pintype "bidirectional"))
      (node (ref "U4") (pin "4") (pinfunction "P1_4") (pintype "input"))
      (node (ref "U5") (pin "4") (pinfunction "P1_4") (pintype "input"))
    )
    (net (code "4") (name "/A2") (class "Default")
      (node (ref "U2") (pin "16") (pinfunction "B3_16") (pintype "bidirectional"))
      (node (ref "U4") (pin "6") (pinfunction "P2_6") (pintype "input"))
      (node (ref "U5") (pin "6") (pinfunction "P2_6") (pintype "input"))
    )
    (net (code "5") (name "/A3") (class "Default")
      (node (ref "U2") (pin "15") (pinfunction "B4_15") (pintype "bidirectional"))
      (node (ref "U4") (pin "8") (pinfunction "P3_8") (pintype "input"))
      (node (ref "U5") (pin "8") (pinfunction "P3_8") (pintype "input"))
    )
    (net (code "6") (name "/A4") (class "Default")
      (node (ref "U2") (pin "14") (pinfunction "B5_14") (pintype "bidirectional"))
      (node (ref "U4") (pin "11") (pinfunction "P4_11") (pintype "input"))
      (node (ref "U5") (pin "11") (pinfunction "P4_11") (pintype "input"))
    )
    (net (code "7") (name "/A5") (class "Default")
      (node (ref "U2") (pin "13") (pinfunction "B6_13") (pintype "bidirectional"))
      (node (ref "U4") (pin "13") (pinfunction "P5_13") (pintype "input"))
      (node (ref "U5") (pin "13") (pinfunction "P5_13") (pintype "input"))
    )
    (net (code "8") (name "/A6") (class "Default")
      (node (ref "U2") (pin "12") (pinfunction "B7_12") (pintype "bidirectional"))
      (node (ref "U4") (pin "15") (pinfunction "P6_15") (pintype "input"))
      (node (ref "U5") (pin "15") (pinfunction "P6_15") (pintype "input"))
    )
    (net (code "9") (name "/A7") (class "Default")
      (node (ref "U2") (pin "11") (pinfunction "B8_11") (pintype "bidirectional"))
      (node (ref "U4") (pin "17") (pinfunction "P7_17") (pintype "input"))
      (node (ref "U5") (pin "17") (pinfunction "P7_17") (pintype "input"))
    )
    (net (code "10") (name "/CLK") (class "Default")
      (node (ref "U3") (pin "11") (pinfunction "B8_11") (pintype "bidirectional"))
      (node (ref "U8") (pin "13") (pinfunction "I1_13") (pintype "input"))
      (node (ref "U8") (pin "4") (pinfunction "I0_4") (pintype "input"))
    )
    (net (code "11") (name "/COL0_A") (class "Default")
      (node (ref "R10") (pin "1") (pinfunction "1_1") (pintype "passive"))
      (node (ref "U16") (pin "15") (pinfunction "QA_15") (pintype "tri_state"))
    )
    (net (code "12") (name "/COL0_B") (class "Default")
      (node (ref "R25") (pin "1") (pinfunction "1_1") (pintype "passive"))
      (node (ref "U17") (pin "7") (pinfunction "QH_7") (pintype "tri_state"))
    )
    (net (code "13") (name "/COL0_C") (class "Default")
      (node (ref "R23") (pin "1") (pinfunction "1_1") (pintype "passive"))
      (node (ref "U17") (pin "5") (pinfunction "QF_5") (pintype "tri_state"))
    )
    (net (code "14") (name "/COL0_D") (class "Default")
      (node (ref "R20") (pin "1") (pinfunction "1_1") (pintype "passive"))
      (node (ref "U17") (pin "2") (pinfunction "QC_2") (pintype "tri_state"))
    )
    (net (code "15") (name "/COL0_E") (class "Default")
      (node (ref "R19") (pin "1") (pinfunction "1_1") (pintype "passive"))
      (node (ref "U17") (pin "1") (pinfunction "QB_1") (pintype "tri_state"))
    )
    (net (code "16") (name "/COL0_F") (class "Default")
      (node (ref "R18") (pin "1") (pinfunction "1_1") (pintype "passive"))
      (node (ref "U17") (pin "15") (pinfunction "QA_15") (pintype "tri_state"))
    )
    (net (code "17") (name "/COL0_G") (class "Default")
      (node (ref "R17") (pin "1") (pinfunction "1_1") (pintype "passive"))
      (node (ref "U16") (pin "7") (pinfunction "QH_7") (pintype "tri_state"))
    )
    (net (code "18") (name "/COL0_H") (class "Default")
      (node (ref "R13") (pin "1") (pinfunction "1_1") (pintype "passive"))
      (node (ref "U16") (pin "3") (pinfunction "QD_3") (pintype "tri_state"))
    )
    (net (code "19") (name "/COL0_K") (class "Default")
      (node (ref "R12") (pin "1") (pinfunction "1_1") (pintype "passive"))
      (node (ref "U16") (pin "2") (pinfunction "QC_2") (pintype "tri_state"))
    )
    (net (code "20") (name "/COL0_M") (class "Default")
      (node (ref "R11") (pin "1") (pinfunction "1_1") (pintype "passive"))
      (node (ref "U16") (pin "1") (pinfunction "QB_1") (pintype "tri_state"))
    )
    (net (code "21") (name "/COL0_N") (class "Default")
      (node (ref "R24") (pin "1") (pinfunction "1_1") (pintype "passive"))
      (node (ref "U17") (pin "6") (pinfunction "QG_6") (pintype "tri_state"))
    )
    (net (code "22") (name "/COL0_P") (class "Default")
      (node (ref "R22") (pin "1") (pinfunction "1_1") (pintype "passive"))
      (node (ref "U17") (pin "4") (pinfunction "QE_4") (pintype "tri_state"))
    )
    (net (code "23") (name "/COL0_R") (class "Default")
      (node (ref "R21") (pin "1") (pinfunction "1_1") (pintype "passive"))
      (node (ref "U17") (pin "3") (pinfunction "QD_3") (pintype "tri_state"))
    )
    (net (code "24") (name "/COL0_S") (class "Default")
      (node (ref "R15") (pin "1") (pinfunction "1_1") (pintype "passive"))
      (node (ref "U16") (pin "5") (pinfunction "QF_5") (pintype "tri_state"))
    )
    (net (code "25") (name "/COL0_T") (class "Default")
      (node (ref "R16") (pin "1") (pinfunction "1_1") (pintype "passive"))
      (node (ref "U16") (pin "6") (pinfunction "QG_6") (pintype "tri_state"))
    )
    (net (code "26") (name "/COL0_U") (class "Default")
      (node (ref "R14") (pin "1") (pinfunction "1_1") (pintype "passive"))
      (node (ref "U16") (pin "4") (pinfunction "QE_4") (pintype "tri_state"))
    )
    (net (code "27") (name "/COL1_A") (class "Default")
      (node (ref "R26") (pin "1") (pinfunction "1_1") (pintype "passive"))
      (node (ref "U18") (pin "15") (pinfunction "QA_15") (pintype "tri_state"))
    )
    (net (code "28") (name "/COL1_B") (class "Default")
      (node (ref "R41") (pin "1") (pinfunction "1_1") (pintype "passive"))
      (node (ref "U19") (pin "7") (pinfunction "QH_7") (pintype "tri_state"))
    )
    (net (code "29") (name "/COL1_C") (class "Default")
      (node (ref "R39") (pin "1") (pinfunction "1_1") (pintype "passive"))
      (node (ref "U19") (pin "5") (pinfunction "QF_5") (pintype "tri_state"))
    )
    (net (code "30") (name "/COL1_D") (class "Default")
      (node (ref "R36") (pin "1") (pinfunction "1_1") (pintype "passive"))
      (node (ref "U19") (pin "2") (pinfunction "QC_2") (pintype "tri_state"))
    )
    (net (code "31") (name "/COL1_E") (class "Default")
      (node (ref "R35") (pin "1") (pinfunction "1_1") (pintype "passive"))
      (node (ref "U19") (pin "1") (pinfunction "QB_1") (pintype "tri_state"))
    )
    (net (code "32") (name "/COL1_F") (class "Default")
      (node (ref "R34") (pin "1") (pinfunction "1_1") (pintype "passive"))
      (node (ref "U19") (pin "15") (pinfunction "QA_15") (pintype "tri_state"))
    )
    (net (code "33") (name "/COL1_G") (class "Default")
      (node (ref "R33") (pin "1") (pinfunction "1_1") (pintype "passive"))
      (node (ref "U18") (pin "7") (pinfunction "QH_7") (pintype "tri_state"))
    )
    (net (code "34") (name "/COL1_H") (class "Default")
      (node (ref "R29") (pin "1") (pinfunction "1_1") (pintype "passive"))
      (node (ref "U18") (pin "3") (pinfunction "QD_3") (pintype "tri_state"))
    )
    (net (code "35") (name "/COL1_K") (class "Default")
      (node (ref "R28") (pin "1") (pinfunction "1_1") (pintype "passive"))
      (node (ref "U18") (pin "2") (pinfunction "QC_2") (pintype "tri_state"))
    )
    (net (code "36") (name "/COL1_M") (class "Default")
      (node (ref "R27") (pin "1") (pinfunction "1_1") (pintype "passive"))
      (node (ref "U18") (pin "1") (pinfunction "QB_1") (pintype "tri_state"))
    )
    (net (code "37") (name "/COL1_N") (class "Default")
      (node (ref "R40") (pin "1") (pinfunction "1_1") (pintype "passive"))
      (node (ref "U19") (pin "6") (pinfunction "QG_6") (pintype "tri_state"))
    )
    (net (code "38") (name "/COL1_P") (class "Default")
      (node (ref "R38") (pin "1") (pinfunction "1_1") (pintype "passive"))
      (node (ref "U19") (pin "4") (pinfunction "QE_4") (pintype "tri_state"))
    )
    (net (code "39") (name "/COL1_R") (class "Default")
      (node (ref "R37") (pin "1") (pinfunction "1_1") (pintype "passive"))
      (node (ref "U19") (pin "3") (pinfunction "QD_3") (pintype "tri_state"))
    )
    (net (code "40") (name "/COL1_S") (class "Default")
      (node (ref "R31") (pin "1") (pinfunction "1_1") (pintype "passive"))
      (node (ref "U18") (pin "5") (pinfunction "QF_5") (pintype "tri_state"))
    )
    (net (code "41") (name "/COL1_T") (class "Default")
      (node (ref "R32") (pin "1") (pinfunction "1_1") (pintype "passive"))
      (node (ref "U18") (pin "6") (pinfunction "QG_6") (pintype "tri_state"))
    )
    (net (code "42") (name "/COL1_U") (class "Default")
      (node (ref "R30") (pin "1") (pinfunction "1_1") (pintype "passive"))
      (node (ref "U18") (pin "4") (pinfunction "QE_4") (pintype "tri_state"))
    )
    (net (code "43") (name "/COL2_A") (class "Default")
      (node (ref "R42") (pin "1") (pinfunction "1_1") (pintype "passive"))
      (node (ref "U20") (pin "15") (pinfunction "QA_15") (pintype "tri_state"))
    )
    (net (code "44") (name "/COL2_B") (class "Default")
      (node (ref "R57") (pin "1") (pinfunction "1_1") (pintype "passive"))
      (node (ref "U21") (pin "7") (pinfunction "QH_7") (pintype "tri_state"))
    )
    (net (code "45") (name "/COL2_C") (class "Default")
      (node (ref "R55") (pin "1") (pinfunction "1_1") (pintype "passive"))
      (node (ref "U21") (pin "5") (pinfunction "QF_5") (pintype "tri_state"))
    )
    (net (code "46") (name "/COL2_D") (class "Default")
      (node (ref "R52") (pin "1") (pinfunction "1_1") (pintype "passive"))
      (node (ref "U21") (pin "2") (pinfunction "QC_2") (pintype "tri_state"))
    )
    (net (code "47") (name "/COL2_E") (class "Default")
      (node (ref "R51") (pin "1") (pinfunction "1_1") (pintype "passive"))
      (node (ref "U21") (pin "1") (pinfunction "QB_1") (pintype "tri_state"))
    )
    (net (code "48") (name "/COL2_F") (class "Default")
      (node (ref "R50") (pin "1") (pinfunction "1_1") (pintype "passive"))
      (node (ref "U21") (pin "15") (pinfunction "QA_15") (pintype "tri_state"))
    )
    (net (code "49") (name "/COL2_G") (class "Default")
      (node (ref "R49") (pin "1") (pinfunction "1_1") (pintype "passive"))
      (node (ref "U20") (pin "7") (pinfunction "QH_7") (pintype "tri_state"))
    )
    (net (code "50") (name "/COL2_H") (class "Default")
      (node (ref "R45") (pin "1") (pinfunction "1_1") (pintype "passive"))
      (node (ref "U20") (pin "3") (pinfunction "QD_3") (pintype "tri_state"))
    )
    (net (code "51") (name "/COL2_K") (class "Default")
      (node (ref "R44") (pin "1") (pinfunction "1_1") (pintype "passive"))
      (node (ref "U20") (pin "2") (pinfunction "QC_2") (pintype "tri_state"))
    )
    (net (code "52") (name "/COL2_M") (class "Default")
      (node (ref "R43") (pin "1") (pinfunction "1_1") (pintype "passive"))
      (node (ref "U20") (pin "1") (pinfunction "QB_1") (pintype "tri_state"))
    )
    (net (code "53") (name "/COL2_N") (class "Default")
      (node (ref "R56") (pin "1") (pinfunction "1_1") (pintype "passive"))
      (node (ref "U21") (pin "6") (pinfunction "QG_6") (pintype "tri_state"))
    )
    (net (code "54") (name "/COL2_P") (class "Default")
      (node (ref "R54") (pin "1") (pinfunction "1_1") (pintype "passive"))
      (node (ref "U21") (pin "4") (pinfunction "QE_4") (pintype "tri_state"))
    )
    (net (code "55") (name "/COL2_R") (class "Default")
      (node (ref "R53") (pin "1") (pinfunction "1_1") (pintype "passive"))
      (node (ref "U21") (pin "3") (pinfunction "QD_3") (pintype "tri_state"))
    )
    (net (code "56") (name "/COL2_S") (class "Default")
      (node (ref "R47") (pin "1") (pinfunction "1_1") (pintype "passive"))
      (node (ref "U20") (pin "5") (pinfunction "QF_5") (pintype "tri_state"))
    )
    (net (code "57") (name "/COL2_T") (class "Default")
      (node (ref "R48") (pin "1") (pinfunction "1_1") (pintype "passive"))
      (node (ref "U20") (pin "6") (pinfunction "QG_6") (pintype "tri_state"))
    )
    (net (code "58") (name "/COL2_U") (class "Default")
      (node (ref "R46") (pin "1") (pinfunction "1_1") (pintype "passive"))
      (node (ref "U20") (pin "4") (pinfunction "QE_4") (pintype "tri_state"))
    )
    (net (code "59") (name "/COL3_A") (class "Default")
      (node (ref "R58") (pin "1") (pinfunction "1_1") (pintype "passive"))
      (node (ref "U22") (pin "15") (pinfunction "QA_15") (pintype "tri_state"))
    )
    (net (code "60") (name "/COL3_B") (class "Default")
      (node (ref "R73") (pin "1") (pinfunction "1_1") (pintype "passive"))
      (node (ref "U23") (pin "7") (pinfunction "QH_7") (pintype "tri_state"))
    )
    (net (code "61") (name "/COL3_C") (class "Default")
      (node (ref "R71") (pin "1") (pinfunction "1_1") (pintype "passive"))
      (node (ref "U23") (pin "5") (pinfunction "QF_5") (pintype "tri_state"))
    )
    (net (code "62") (name "/COL3_D") (class "Default")
      (node (ref "R68") (pin "1") (pinfunction "1_1") (pintype "passive"))
      (node (ref "U23") (pin "2") (pinfunction "QC_2") (pintype "tri_state"))
    )
    (net (code "63") (name "/COL3_E") (class "Default")
      (node (ref "R67") (pin "1") (pinfunction "1_1") (pintype "passive"))
      (node (ref "U23") (pin "1") (pinfunction "QB_1") (pintype "tri_state"))
    )
    (net (code "64") (name "/COL3_F") (class "Default")
      (node (ref "R66") (pin "1") (pinfunction "1_1") (pintype "passive"))
      (node (ref "U23") (pin "15") (pinfunction "QA_15") (pintype "tri_state"))
    )
    (net (code "65") (name "/COL3_G") (class "Default")
      (node (ref "R65") (pin "1") (pinfunction "1_1") (pintype "passive"))
      (node (ref "U22") (pin "7") (pinfunction "QH_7") (pintype "tri_state"))
    )
    (net (code "66") (name "/COL3_H") (class "Default")
      (node (ref "R61") (pin "1") (pinfunction "1_1") (pintype "passive"))
      (node (ref "U22") (pin "3") (pinfunction "QD_3") (pintype "tri_state"))
    )
    (net (code "67") (name "/COL3_K") (class "Default")
      (node (ref "R60") (pin "1") (pinfunction "1_1") (pintype "passive"))
      (node (ref "U22") (pin "2") (pinfunction "QC_2") (pintype "tri_state"))
    )
    (net (code "68") (name "/COL3_M") (class "Default")
      (node (ref "R59") (pin "1") (pinfunction "1_1") (pintype "passive"))
      (node (ref "U22") (pin "1") (pinfunction "QB_1") (pintype "tri_state"))
    )
    (net (code "69") (name "/COL3_N") (class "Default")
      (node (ref "R72") (pin "1") (pinfunction "1_1") (pintype "passive"))
      (node (ref "U23") (pin "6") (pinfunction "QG_6") (pintype "tri_state"))
    )
    (net (code "70") (name "/COL3_P") (class "Default")
      (node (ref "R70") (pin "1") (pinfunction "1_1") (pintype "passive"))
      (node (ref "U23") (pin "4") (pinfunction "QE_4") (pintype "tri_state"))
    )
    (net (code "71") (name "/COL3_R") (class "Default")
      (node (ref "R69") (pin "1") (pinfunction "1_1") (pintype "passive"))
      (node (ref "U23") (pin "3") (pinfunction "QD_3") (pintype "tri_state"))
    )
    (net (code "72") (name "/COL3_S") (class "Default")
      (node (ref "R63") (pin "1") (pinfunction "1_1") (pintype "passive"))
      (node (ref "U22") (pin "5") (pinfunction "QF_5") (pintype "tri_state"))
    )
    (net (code "73") (name "/COL3_T") (class "Default")
      (node (ref "R64") (pin "1") (pinfunction "1_1") (pintype "passive"))
      (node (ref "U22") (pin "6") (pinfunction "QG_6") (pintype "tri_state"))
    )
    (net (code "74") (name "/COL3_U") (class "Default")
      (node (ref "R62") (pin "1") (pinfunction "1_1") (pintype "passive"))
      (node (ref "U22") (pin "4") (pinfunction "QE_4") (pintype "tri_state"))
    )
    (net (code "75") (name "/COL4_A") (class "Default")
      (node (ref "R74") (pin "1") (pinfunction "1_1") (pintype "passive"))
      (node (ref "U24") (pin "15") (pinfunction "QA_15") (pintype "tri_state"))
    )
    (net (code "76") (name "/COL4_B") (class "Default")
      (node (ref "R89") (pin "1") (pinfunction "1_1") (pintype "passive"))
      (node (ref "U25") (pin "7") (pinfunction "QH_7") (pintype "tri_state"))
    )
    (net (code "77") (name "/COL4_C") (class "Default")
      (node (ref "R87") (pin "1") (pinfunction "1_1") (pintype "passive"))
      (node (ref "U25") (pin "5") (pinfunction "QF_5") (pintype "tri_state"))
    )
    (net (code "78") (name "/COL4_D") (class "Default")
      (node (ref "R84") (pin "1") (pinfunction "1_1") (pintype "passive"))
      (node (ref "U25") (pin "2") (pinfunction "QC_2") (pintype "tri_state"))
    )
    (net (code "79") (name "/COL4_E") (class "Default")
      (node (ref "R83") (pin "1") (pinfunction "1_1") (pintype "passive"))
      (node (ref "U25") (pin "1") (pinfunction "QB_1") (pintype "tri_state"))
    )
    (net (code "80") (name "/COL4_F") (class "Default")
      (node (ref "R82") (pin "1") (pinfunction "1_1") (pintype "passive"))
      (node (ref "U25") (pin "15") (pinfunction "QA_15") (pintype "tri_state"))
    )
    (net (code "81") (name "/COL4_G") (class "Default")
      (node (ref "R81") (pin "1") (pinfunction "1_1") (pintype "passive"))
      (node (ref "U24") (pin "7") (pinfunction "QH_7") (pintype "tri_state"))
    )
    (net (code "82") (name "/COL4_H") (class "Default")
      (node (ref "R77") (pin "1") (pinfunction "1_1") (pintype "passive"))
      (node (ref "U24") (pin "3") (pinfunction "QD_3") (pintype "tri_state"))
    )
    (net (code "83") (name "/COL4_K") (class "Default")
      (node (ref "R76") (pin "1") (pinfunction "1_1") (pintype "passive"))
      (node (ref "U24") (pin "2") (pinfunction "QC_2") (pintype "tri_state"))
    )
    (net (code "84") (name "/COL4_M") (class "Default")
      (node (ref "R75") (pin "1") (pinfunction "1_1") (pintype "passive"))
      (node (ref "U24") (pin "1") (pinfunction "QB_1") (pintype "tri_state"))
    )
    (net (code "85") (name "/COL4_N") (class "Default")
      (node (ref "R88") (pin "1") (pinfunction "1_1") (pintype "passive"))
      (node (ref "U25") (pin "6") (pinfunction "QG_6") (pintype "tri_state"))
    )
    (net (code "86") (name "/COL4_P") (class "Default")
      (node (ref "R86") (pin "1") (pinfunction "1_1") (pintype "passive"))
      (node (ref "U25") (pin "4") (pinfunction "QE_4") (pintype "tri_state"))
    )
    (net (code "87") (name "/COL4_R") (class "Default")
      (node (ref "R85") (pin "1") (pinfunction "1_1") (pintype "passive"))
      (node (ref "U25") (pin "3") (pinfunction "QD_3") (pintype "tri_state"))
    )
    (net (code "88") (name "/COL4_S") (class "Default")
      (node (ref "R79") (pin "1") (pinfunction "1_1") (pintype "passive"))
      (node (ref "U24") (pin "5") (pinfunction "QF_5") (pintype "tri_state"))
    )
    (net (code "89") (name "/COL4_T") (class "Default")
      (node (ref "R80") (pin "1") (pinfunction "1_1") (pintype "passive"))
      (node (ref "U24") (pin "6") (pinfunction "QG_6") (pintype "tri_state"))
    )
    (net (code "90") (name "/COL4_U") (class "Default")
      (node (ref "R78") (pin "1") (pinfunction "1_1") (pintype "passive"))
      (node (ref "U24") (pin "4") (pinfunction "QE_4") (pintype "tri_state"))
    )
    (net (code "91") (name "/COL5\\_B") (class "Default")
      (node (ref "R105") (pin "1") (pinfunction "1_1") (pintype "passive"))
      (node (ref "U27") (pin "7") (pinfunction "QH_7") (pintype "tri_state"))
    )
    (net (code "92") (name "/COL5_A") (class "Default")
      (node (ref "R90") (pin "1") (pinfunction "1_1") (pintype "passive"))
      (node (ref "U26") (pin "15") (pinfunction "QA_15") (pintype "tri_state"))
    )
    (net (code "93") (name "/COL5_C") (class "Default")
      (node (ref "R103") (pin "1") (pinfunction "1_1") (pintype "passive"))
      (node (ref "U27") (pin "5") (pinfunction "QF_5") (pintype "tri_state"))
    )
    (net (code "94") (name "/COL5_D") (class "Default")
      (node (ref "R100") (pin "1") (pinfunction "1_1") (pintype "passive"))
      (node (ref "U27") (pin "2") (pinfunction "QC_2") (pintype "tri_state"))
    )
    (net (code "95") (name "/COL5_E") (class "Default")
      (node (ref "R99") (pin "1") (pinfunction "1_1") (pintype "passive"))
      (node (ref "U27") (pin "1") (pinfunction "QB_1") (pintype "tri_state"))
    )
    (net (code "96") (name "/COL5_F") (class "Default")
      (node (ref "R98") (pin "1") (pinfunction "1_1") (pintype "passive"))
      (node (ref "U27") (pin "15") (pinfunction "QA_15") (pintype "tri_state"))
    )
    (net (code "97") (name "/COL5_G") (class "Default")
      (node (ref "R97") (pin "1") (pinfunction "1_1") (pintype "passive"))
      (node (ref "U26") (pin "7") (pinfunction "QH_7") (pintype "tri_state"))
    )
    (net (code "98") (name "/COL5_H") (class "Default")
      (node (ref "R93") (pin "1") (pinfunction "1_1") (pintype "passive"))
      (node (ref "U26") (pin "3") (pinfunction "QD_3") (pintype "tri_state"))
    )
    (net (code "99") (name "/COL5_K") (class "Default")
      (node (ref "R92") (pin "1") (pinfunction "1_1") (pintype "passive"))
      (node (ref "U26") (pin "2") (pinfunction "QC_2") (pintype "tri_state"))
    )
    (net (code "100") (name "/COL5_M") (class "Default")
      (node (ref "R91") (pin "1") (pinfunction "1_1") (pintype "passive"))
      (node (ref "U26") (pin "1") (pinfunction "QB_1") (pintype "tri_state"))
    )
    (net (code "101") (name "/COL5_N") (class "Default")
      (node (ref "R104") (pin "1") (pinfunction "1_1") (pintype "passive"))
      (node (ref "U27") (pin "6") (pinfunction "QG_6") (pintype "tri_state"))
    )
    (net (code "102") (name "/COL5_P") (class "Default")
      (node (ref "R102") (pin "1") (pinfunction "1_1") (pintype "passive"))
      (node (ref "U27") (pin "4") (pinfunction "QE_4") (pintype "tri_state"))
    )
    (net (code "103") (name "/COL5_R") (class "Default")
      (node (ref "R101") (pin "1") (pinfunction "1_1") (pintype "passive"))
      (node (ref "U27") (pin "3") (pinfunction "QD_3") (pintype "tri_state"))
    )
    (net (code "104") (name "/COL5_S") (class "Default")
      (node (ref "R95") (pin "1") (pinfunction "1_1") (pintype "passive"))
      (node (ref "U26") (pin "5") (pinfunction "QF_5") (pintype "tri_state"))
    )
    (net (code "105") (name "/COL5_T") (class "Default")
      (node (ref "R96") (pin "1") (pinfunction "1_1") (pintype "passive"))
      (node (ref "U26") (pin "6") (pinfunction "QG_6") (pintype "tri_state"))
    )
    (net (code "106") (name "/COL5_U") (class "Default")
      (node (ref "R94") (pin "1") (pinfunction "1_1") (pintype "passive"))
      (node (ref "U26") (pin "4") (pinfunction "QE_4") (pintype "tri_state"))
    )
    (net (code "107") (name "/COL6_A") (class "Default")
      (node (ref "R106") (pin "1") (pinfunction "1_1") (pintype "passive"))
      (node (ref "U28") (pin "15") (pinfunction "QA_15") (pintype "tri_state"))
    )
    (net (code "108") (name "/COL6_B") (class "Default")
      (node (ref "R121") (pin "1") (pinfunction "1_1") (pintype "passive"))
      (node (ref "U29") (pin "7") (pinfunction "QH_7") (pintype "tri_state"))
    )
    (net (code "109") (name "/COL6_C") (class "Default")
      (node (ref "R119") (pin "1") (pinfunction "1_1") (pintype "passive"))
      (node (ref "U29") (pin "5") (pinfunction "QF_5") (pintype "tri_state"))
    )
    (net (code "110") (name "/COL6_D") (class "Default")
      (node (ref "R116") (pin "1") (pinfunction "1_1") (pintype "passive"))
      (node (ref "U29") (pin "2") (pinfunction "QC_2") (pintype "tri_state"))
    )
    (net (code "111") (name "/COL6_E") (class "Default")
      (node (ref "R115") (pin "1") (pinfunction "1_1") (pintype "passive"))
      (node (ref "U29") (pin "1") (pinfunction "QB_1") (pintype "tri_state"))
    )
    (net (code "112") (name "/COL6_F") (class "Default")
      (node (ref "R114") (pin "1") (pinfunction "1_1") (pintype "passive"))
      (node (ref "U29") (pin "15") (pinfunction "QA_15") (pintype "tri_state"))
    )
    (net (code "113") (name "/COL6_G") (class "Default")
      (node (ref "R113") (pin "1") (pinfunction "1_1") (pintype "passive"))
      (node (ref "U28") (pin "7") (pinfunction "QH_7") (pintype "tri_state"))
    )
    (net (code "114") (name "/COL6_H") (class "Default")
      (node (ref "R109") (pin "1") (pinfunction "1_1") (pintype "passive"))
      (node (ref "U28") (pin "3") (pinfunction "QD_3") (pintype "tri_state"))
    )
    (net (code "115") (name "/COL6_K") (class "Default")
      (node (ref "R108") (pin "1") (pinfunction "1_1") (pintype "passive"))
      (node (ref "U28") (pin "2") (pinfunction "QC_2") (pintype "tri_state"))
    )
    (net (code "116") (name "/COL6_M") (class "Default")
      (node (ref "R107") (pin "1") (pinfunction "1_1") (pintype "passive"))
      (node (ref "U28") (pin "1") (pinfunction "QB_1") (pintype "tri_state"))
    )
    (net (code "117") (name "/COL6_N") (class "Default")
      (node (ref "R120") (pin "1") (pinfunction "1_1") (pintype "passive"))
      (node (ref "U29") (pin "6") (pinfunction "QG_6") (pintype "tri_state"))
    )
    (net (code "118") (name "/COL6_P") (class "Default")
      (node (ref "R118") (pin "1") (pinfunction "1_1") (pintype "passive"))
      (node (ref "U29") (pin "4") (pinfunction "QE_4") (pintype "tri_state"))
    )
    (net (code "119") (name "/COL6_R") (class "Default")
      (node (ref "R117") (pin "1") (pinfunction "1_1") (pintype "passive"))
      (node (ref "U29") (pin "3") (pinfunction "QD_3") (pintype "tri_state"))
    )
    (net (code "120") (name "/COL6_S") (class "Default")
      (node (ref "R111") (pin "1") (pinfunction "1_1") (pintype "passive"))
      (node (ref "U28") (pin "5") (pinfunction "QF_5") (pintype "tri_state"))
    )
    (net (code "121") (name "/COL6_T") (class "Default")
      (node (ref "R112") (pin "1") (pinfunction "1_1") (pintype "passive"))
      (node (ref "U28") (pin "6") (pinfunction "QG_6") (pintype "tri_state"))
    )
    (net (code "122") (name "/COL6_U") (class "Default")
      (node (ref "R110") (pin "1") (pinfunction "1_1") (pintype "passive"))
      (node (ref "U28") (pin "4") (pinfunction "QE_4") (pintype "tri_state"))
    )
    (net (code "123") (name "/COL7\\_F") (class "Default")
      (node (ref "R130") (pin "1") (pinfunction "1_1") (pintype "passive"))
      (node (ref "U31") (pin "15") (pinfunction "QA_15") (pintype "tri_state"))
    )
    (net (code "124") (name "/COL7_A") (class "Default")
      (node (ref "R122") (pin "1") (pinfunction "1_1") (pintype "passive"))
      (node (ref "U30") (pin "15") (pinfunction "QA_15") (pintype "tri_state"))
    )
    (net (code "125") (name "/COL7_B") (class "Default")
      (node (ref "R137") (pin "1") (pinfunction "1_1") (pintype "passive"))
      (node (ref "U31") (pin "7") (pinfunction "QH_7") (pintype "tri_state"))
    )
    (net (code "126") (name "/COL7_C") (class "Default")
      (node (ref "R135") (pin "1") (pinfunction "1_1") (pintype "passive"))
      (node (ref "U31") (pin "5") (pinfunction "QF_5") (pintype "tri_state"))
    )
    (net (code "127") (name "/COL7_D") (class "Default")
      (node (ref "R132") (pin "1") (pinfunction "1_1") (pintype "passive"))
      (node (ref "U31") (pin "2") (pinfunction "QC_2") (pintype "tri_state"))
    )
    (net (code "128") (name "/COL7_E") (class "Default")
      (node (ref "R131") (pin "1") (pinfunction "1_1") (pintype "passive"))
      (node (ref "U31") (pin "1") (pinfunction "QB_1") (pintype "tri_state"))
    )
    (net (code "129") (name "/COL7_G") (class "Default")
      (node (ref "R129") (pin "1") (pinfunction "1_1") (pintype "passive"))
      (node (ref "U30") (pin "7") (pinfunction "QH_7") (pintype "tri_state"))
    )
    (net (code "130") (name "/COL7_H") (class "Default")
      (node (ref "R125") (pin "1") (pinfunction "1_1") (pintype "passive"))
      (node (ref "U30") (pin "3") (pinfunction "QD_3") (pintype "tri_state"))
    )
    (net (code "131") (name "/COL7_K") (class "Default")
      (node (ref "R124") (pin "1") (pinfunction "1_1") (pintype "passive"))
      (node (ref "U30") (pin "2") (pinfunction "QC_2") (pintype "tri_state"))
    )
    (net (code "132") (name "/COL7_M") (class "Default")
      (node (ref "R123") (pin "1") (pinfunction "1_1") (pintype "passive"))
      (node (ref "U30") (pin "1") (pinfunction "QB_1") (pintype "tri_state"))
    )
    (net (code "133") (name "/COL7_N") (class "Default")
      (node (ref "R136") (pin "1") (pinfunction "1_1") (pintype "passive"))
      (node (ref "U31") (pin "6") (pinfunction "QG_6") (pintype "tri_state"))
    )
    (net (code "134") (name "/COL7_P") (class "Default")
      (node (ref "R134") (pin "1") (pinfunction "1_1") (pintype "passive"))
      (node (ref "U31") (pin "4") (pinfunction "QE_4") (pintype "tri_state"))
    )
    (net (code "135") (name "/COL7_R") (class "Default")
      (node (ref "R133") (pin "1") (pinfunction "1_1") (pintype "passive"))
      (node (ref "U31") (pin "3") (pinfunction "QD_3") (pintype "tri_state"))
    )
    (net (code "136") (name "/COL7_S") (class "Default")
      (node (ref "R127") (pin "1") (pinfunction "1_1") (pintype "passive"))
      (node (ref "U30") (pin "5") (pinfunction "QF_5") (pintype "tri_state"))
    )
    (net (code "137") (name "/COL7_T") (class "Default")
      (node (ref "R128") (pin "1") (pinfunction "1_1") (pintype "passive"))
      (node (ref "U30") (pin "6") (pinfunction "QG_6") (pintype "tri_state"))
    )
    (net (code "138") (name "/COL7_U") (class "Default")
      (node (ref "R126") (pin "1") (pinfunction "1_1") (pintype "passive"))
      (node (ref "U30") (pin "4") (pinfunction "QE_4") (pintype "tri_state"))
    )
    (net (code "139") (name "/D0") (class "Default")
      (node (ref "U1") (pin "18") (pinfunction "B1_18") (pintype "bidirectional"))
      (node (ref "U11") (pin "2") (pinfunction "A_2") (pintype "input"))
      (node (ref "U13") (pin "2") (pinfunction "1D_2") (pintype "input"))
    )
    (net (code "140") (name "/D1") (class "Default")
      (node (ref "U1") (pin "17") (pinfunction "B2_17") (pintype "bidirectional"))
      (node (ref "U11") (pin "3") (pinfunction "B_3") (pintype "input"))
      (node (ref "U13") (pin "3") (pinfunction "2D_3") (pintype "input"))
    )
    (net (code "141") (name "/D2") (class "Default")
      (node (ref "U1") (pin "16") (pinfunction "B3_16") (pintype "bidirectional"))
      (node (ref "U11") (pin "4") (pinfunction "C_4") (pintype "input"))
      (node (ref "U13") (pin "4") (pinfunction "3D_4") (pintype "input"))
    )
    (net (code "142") (name "/D3") (class "Default")
      (node (ref "U1") (pin "15") (pinfunction "B4_15") (pintype "bidirectional"))
      (node (ref "U11") (pin "5") (pinfunction "D_5") (pintype "input"))
      (node (ref "U13") (pin "5") (pinfunction "4D_5") (pintype "input"))
    )
    (net (code "143") (name "/D4") (class "Default")
      (node (ref "U1") (pin "14") (pinfunction "B5_14") (pintype "bidirectional"))
      (node (ref "U11") (pin "10") (pinfunction "E_10") (pintype "input"))
      (node (ref "U13") (pin "6") (pinfunction "5D_6") (pintype "input"))
    )
    (net (code "144") (name "/D5") (class "Default")
      (node (ref "U1") (pin "13") (pinfunction "B6_13") (pintype "bidirectional"))
      (node (ref "U11") (pin "11") (pinfunction "F_11") (pintype "input"))
      (node (ref "U13") (pin "7") (pinfunction "6D_7") (pintype "input"))
    )
    (net (code "145") (name "/D6") (class "Default")
      (node (ref "U1") (pin "12") (pinfunction "B7_12") (pintype "bidirectional"))
      (node (ref "U11") (pin "12") (pinfunction "G_12") (pintype "input"))
      (node (ref "U13") (pin "8") (pinfunction "7D_8") (pintype "input"))
    )
    (net (code "146") (name "/D7") (class "Default")
      (node (ref "U1") (pin "11") (pinfunction "B8_11") (pintype "bidirectional"))
      (node (ref "U11") (pin "14") (pinfunction "H_14") (pintype "input"))
      (node (ref "U13") (pin "9") (pinfunction "8D_9") (pintype "input"))
    )
    (net (code "147") (name "/DP0") (class "Default")
      (node (ref "R2") (pin "1") (pinfunction "1_1") (pintype "passive"))
      (node (ref "U15") (pin "15") (pinfunction "QA_15") (pintype "tri_state"))
    )
    (net (code "148") (name "/DP1") (class "Default")
      (node (ref "R3") (pin "1") (pinfunction "1_1") (pintype "passive"))
      (node (ref "U15") (pin "1") (pinfunction "QB_1") (pintype "tri_state"))
    )
    (net (code "149") (name "/DP2") (class "Default")
      (node (ref "R4") (pin "1") (pinfunction "1_1") (pintype "passive"))
      (node (ref "U15") (pin "2") (pinfunction "QC_2") (pintype "tri_state"))
    )
    (net (code "150") (name "/DP3") (class "Default")
      (node (ref "R5") (pin "1") (pinfunction "1_1") (pintype "passive"))
      (node (ref "U15") (pin "3") (pinfunction "QD_3") (pintype "tri_state"))
    )
    (net (code "151") (name "/DP4") (class "Default")
      (node (ref "R6") (pin "1") (pinfunction "1_1") (pintype "passive"))
      (node (ref "U15") (pin "4") (pinfunction "QE_4") (pintype "tri_state"))
    )
    (net (code "152") (name "/DP5") (class "Default")
      (node (ref "R7") (pin "1") (pinfunction "1_1") (pintype "passive"))
      (node (ref "U15") (pin "5") (pinfunction "QF_5") (pintype "tri_state"))
    )
    (net (code "153") (name "/DP6") (class "Default")
      (node (ref "R8") (pin "1") (pinfunction "1_1") (pintype "passive"))
      (node (ref "U15") (pin "6") (pinfunction "QG_6") (pintype "tri_state"))
    )
    (net (code "154") (name "/DP7") (class "Default")
      (node (ref "R9") (pin "1") (pinfunction "1_1") (pintype "passive"))
      (node (ref "U15") (pin "7") (pinfunction "QH_7") (pintype "tri_state"))
    )
    (net (code "155") (name "/ROW0") (class "Default")
      (node (ref "SV4") (pin "34") (pinfunction "S_34") (pintype "passive"))
      (node (ref "U14") (pin "14") (pinfunction "Y1_14") (pintype "output"))
    )
    (net (code "156") (name "/ROW1") (class "Default")
      (node (ref "SV4") (pin "35") (pinfunction "S_35") (pintype "passive"))
      (node (ref "U14") (pin "13") (pinfunction "Y2_13") (pintype "output"))
    )
    (net (code "157") (name "/ROW2") (class "Default")
      (node (ref "SV4") (pin "36") (pinfunction "S_36") (pintype "passive"))
      (node (ref "U14") (pin "12") (pinfunction "Y3_12") (pintype "output"))
    )
    (net (code "158") (name "/~{G}") (class "Default")
      (node (ref "R1") (pin "2") (pinfunction "2_2") (pintype "passive"))
      (node (ref "U15") (pin "13") (pinfunction "G_13") (pintype "input"))
      (node (ref "U16") (pin "13") (pinfunction "G_13") (pintype "input"))
      (node (ref "U17") (pin "13") (pinfunction "G_13") (pintype "input"))
      (node (ref "U18") (pin "13") (pinfunction "G_13") (pintype "input"))
      (node (ref "U19") (pin "13") (pinfunction "G_13") (pintype "input"))
      (node (ref "U20") (pin "13") (pinfunction "G_13") (pintype "input"))
      (node (ref "U21") (pin "13") (pinfunction "G_13") (pintype "input"))
      (node (ref "U22") (pin "13") (pinfunction "G_13") (pintype "input"))
      (node (ref "U23") (pin "13") (pinfunction "G_13") (pintype "input"))
      (node (ref "U24") (pin "13") (pinfunction "G_13") (pintype "input"))
      (node (ref "U25") (pin "13") (pinfunction "G_13") (pintype "input"))
      (node (ref "U26") (pin "13") (pinfunction "G_13") (pintype "input"))
      (node (ref "U27") (pin "13") (pinfunction "G_13") (pintype "input"))
      (node (ref "U28") (pin "13") (pinfunction "G_13") (pintype "input"))
      (node (ref "U29") (pin "13") (pinfunction "G_13") (pintype "input"))
      (node (ref "U30") (pin "13") (pinfunction "G_13") (pintype "input"))
      (node (ref "U31") (pin "13") (pinfunction "G_13") (pintype "input"))
    )
    (net (code "159") (name "/~{INT}") (class "Default")
      (node (ref "BUS") (pin "11") (pinfunction "S_11") (pintype "passive"))
    )
    (net (code "160") (name "/~{IORQ}") (class "Default")
      (node (ref "U10") (pin "1") (pinfunction "I0_1") (pintype "input"))
      (node (ref "U3") (pin "16") (pinfunction "B3_16") (pintype "bidirectional"))
    )
    (net (code "161") (name "/~{NMI}") (class "Default")
      (node (ref "BUS") (pin "12") (pinfunction "S_12") (pintype "passive"))
    )
    (net (code "162") (name "/~{RESET}") (class "Default")
      (node (ref "U12") (pin "1") (pinfunction "I0_1") (pintype "input"))
      (node (ref "U12") (pin "4") (pinfunction "I0_4") (pintype "input"))
      (node (ref "U15") (pin "10") (pinfunction "SCL_10") (pintype "input"))
      (node (ref "U16") (pin "10") (pinfunction "SCL_10") (pintype "input"))
      (node (ref "U17") (pin "10") (pinfunction "SCL_10") (pintype "input"))
      (node (ref "U18") (pin "10") (pinfunction "SCL_10") (pintype "input"))
      (node (ref "U19") (pin "10") (pinfunction "SCL_10") (pintype "input"))
      (node (ref "U20") (pin "10") (pinfunction "SCL_10") (pintype "input"))
      (node (ref "U21") (pin "10") (pinfunction "SCL_10") (pintype "input"))
      (node (ref "U22") (pin "10") (pinfunction "SCL_10") (pintype "input"))
      (node (ref "U23") (pin "10") (pinfunction "SCL_10") (pintype "input"))
      (node (ref "U24") (pin "10") (pinfunction "SCL_10") (pintype "input"))
      (node (ref "U25") (pin "10") (pinfunction "SCL_10") (pintype "input"))
      (node (ref "U26") (pin "10") (pinfunction "SCL_10") (pintype "input"))
      (node (ref "U27") (pin "10") (pinfunction "SCL_10") (pintype "input"))
      (node (ref "U28") (pin "10") (pinfunction "SCL_10") (pintype "input"))
      (node (ref "U29") (pin "10") (pinfunction "SCL_10") (pintype "input"))
      (node (ref "U3") (pin "12") (pinfunction "B7_12") (pintype "bidirectional"))
      (node (ref "U30") (pin "10") (pinfunction "SCL_10") (pintype "input"))
      (node (ref "U31") (pin "10") (pinfunction "SCL_10") (pintype "input"))
      (node (ref "U8") (pin "1") (pinfunction "I0_1") (pintype "input"))
    )
    (net (code "163") (name "/~{WAIT}") (class "Default")
      (node (ref "BUS") (pin "10") (pinfunction "S_10") (pintype "passive"))
    )
    (net (code "164") (name "/~{WR}") (class "Default")
      (node (ref "U10") (pin "2") (pinfunction "I1_2") (pintype "input"))
      (node (ref "U3") (pin "14") (pinfunction "B5_14") (pintype "bidirectional"))
    )
    (net (code "165") (name "GND") (class "Default")
      (node (ref "BUS") (pin "1") (pinfunction "S_1") (pintype "passive"))
      (node (ref "BUS") (pin "3") (pinfunction "S_3") (pintype "passive"))
      (node (ref "BUS") (pin "31") (pinfunction "S_31") (pintype "passive"))
      (node (ref "BUS") (pin "32") (pinfunction "S_32") (pintype "passive"))
      (node (ref "C1") (pin "-") (pinfunction "-_-") (pintype "passive"))
      (node (ref "C10") (pin "2") (pinfunction "2_2") (pintype "passive"))
      (node (ref "C11") (pin "2") (pinfunction "2_2") (pintype "passive"))
      (node (ref "C12") (pin "2") (pinfunction "2_2") (pintype "passive"))
      (node (ref "C13") (pin "2") (pinfunction "2_2") (pintype "passive"))
      (node (ref "C14") (pin "2") (pinfunction "2_2") (pintype "passive"))
      (node (ref "C15") (pin "2") (pinfunction "2_2") (pintype "passive"))
      (node (ref "C16") (pin "2") (pinfunction "2_2") (pintype "passive"))
      (node (ref "C17") (pin "2") (pinfunction "2_2") (pintype "passive"))
      (node (ref "C18") (pin "2") (pinfunction "2_2") (pintype "passive"))
      (node (ref "C19") (pin "2") (pinfunction "2_2") (pintype "passive"))
      (node (ref "C20") (pin "2") (pinfunction "2_2") (pintype "passive"))
      (node (ref "C21") (pin "2") (pinfunction "2_2") (pintype "passive"))
      (node (ref "C22") (pin "2") (pinfunction "2_2") (pintype "passive"))
      (node (ref "C23") (pin "2") (pinfunction "2_2") (pintype "passive"))
      (node (ref "C24") (pin "2") (pinfunction "2_2") (pintype "passive"))
      (node (ref "C25") (pin "2") (pinfunction "2_2") (pintype "passive"))
      (node (ref "C26") (pin "2") (pinfunction "2_2") (pintype "passive"))
      (node (ref "C27") (pin "2") (pinfunction "2_2") (pintype "passive"))
      (node (ref "C28") (pin "2") (pinfunction "2_2") (pintype "passive"))
      (node (ref "C29") (pin "2") (pinfunction "2_2") (pintype "passive"))
      (node (ref "C3") (pin "2") (pinfunction "2_2") (pintype "passive"))
      (node (ref "C30") (pin "2") (pinfunction "2_2") (pintype "passive"))
      (node (ref "C31") (pin "2") (pinfunction "2_2") (pintype "passive"))
      (node (ref "C32") (pin "2") (pinfunction "2_2") (pintype "passive"))
      (node (ref "C33") (pin "2") (pinfunction "2_2") (pintype "passive"))
      (node (ref "C4") (pin "2") (pinfunction "2_2") (pintype "passive"))
      (node (ref "C5") (pin "2") (pinfunction "2_2") (pintype "passive"))
      (node (ref "C6") (pin "2") (pinfunction "2_2") (pintype "passive"))
      (node (ref "C7") (pin "2") (pinfunction "2_2") (pintype "passive"))
      (node (ref "C8") (pin "2") (pinfunction "2_2") (pintype "passive"))
      (node (ref "C9") (pin "2") (pinfunction "2_2") (pintype "passive"))
      (node (ref "R1") (pin "1") (pinfunction "1_1") (pintype "passive"))
      (node (ref "SV4") (pin "37") (pinfunction "S_37") (pintype "passive"))
      (node (ref "SV4") (pin "39") (pinfunction "S_39") (pintype "passive"))
      (node (ref "U1") (pin "10") (pinfunction "GND_10") (pintype "power_in"))
      (node (ref "U1") (pin "19") (pinfunction "G_19") (pintype "input"))
      (node (ref "U10") (pin "10") (pinfunction "I1_10") (pintype "input"))
      (node (ref "U10") (pin "12") (pinfunction "I0_12") (pintype "input"))
      (node (ref "U10") (pin "13") (pinfunction "I1_13") (pintype "input"))
      (node (ref "U10") (pin "7") (pinfunction "GND_7") (pintype "power_in"))
      (node (ref "U10") (pin "9") (pinfunction "I0_9") (pintype "input"))
      (node (ref "U11") (pin "1") (pinfunction "SER_1") (pintype "input"))
      (node (ref "U11") (pin "6") (pinfunction "INH_6") (pintype "input"))
      (node (ref "U11") (pin "8") (pinfunction "GND_8") (pintype "power_in"))
      (node (ref "U12") (pin "10") (pinfunction "I1_10") (pintype "input"))
      (node (ref "U12") (pin "12") (pinfunction "I0_12") (pintype "input"))
      (node (ref "U12") (pin "13") (pinfunction "I1_13") (pintype "input"))
      (node (ref "U12") (pin "7") (pinfunction "GND_7") (pintype "power_in"))
      (node (ref "U12") (pin "9") (pinfunction "I0_9") (pintype "input"))
      (node (ref "U13") (pin "1") (pinfunction "OC_1") (pintype "input"))
      (node (ref "U13") (pin "10") (pinfunction "GND_10") (pintype "power_in"))
      (node (ref "U14") (pin "3") (pinfunction "C_3") (pintype "input"))
      (node (ref "U14") (pin "4") (pinfunction "G2A_4") (pintype "input"))
      (node (ref "U14") (pin "5") (pinfunction "G2B_5") (pintype "input"))
      (node (ref "U14") (pin "8") (pinfunction "GND_8") (pintype "power_in"))
      (node (ref "U15") (pin "8") (pinfunction "GND_8") (pintype "power_in"))
      (node (ref "U16") (pin "8") (pinfunction "GND_8") (pintype "power_in"))
      (node (ref "U17") (pin "8") (pinfunction "GND_8") (pintype "power_in"))
      (node (ref "U18") (pin "8") (pinfunction "GND_8") (pintype "power_in"))
      (node (ref "U19") (pin "8") (pinfunction "GND_8") (pintype "power_in"))
      (node (ref "U2") (pin "10") (pinfunction "GND_10") (pintype "power_in"))
      (node (ref "U2") (pin "19") (pinfunction "G_19") (pintype "input"))
      (node (ref "U20") (pin "8") (pinfunction "GND_8") (pintype "power_in"))
      (node (ref "U21") (pin "8") (pinfunction "GND_8") (pintype "power_in"))
      (node (ref "U22") (pin "8") (pinfunction "GND_8") (pintype "power_in"))
      (node (ref "U23") (pin "8") (pinfunction "GND_8") (pintype "power_in"))
      (node (ref "U24") (pin "8") (pinfunction "GND_8") (pintype "power_in"))
      (node (ref "U25") (pin "8") (pinfunction "GND_8") (pintype "power_in"))
      (node (ref "U26") (pin "8") (pinfunction "GND_8") (pintype "power_in"))
      (node (ref "U27") (pin "8") (pinfunction "GND_8") (pintype "power_in"))
      (node (ref "U28") (pin "8") (pinfunction "GND_8") (pintype "power_in"))
      (node (ref "U29") (pin "8") (pinfunction "GND_8") (pintype "power_in"))
      (node (ref "U3") (pin "10") (pinfunction "GND_10") (pintype "power_in"))
      (node (ref "U3") (pin "19") (pinfunction "G_19") (pintype "input"))
      (node (ref "U3") (pin "7") (pinfunction "A6_7") (pintype "bidirectional"))
      (node (ref "U30") (pin "8") (pinfunction "GND_8") (pintype "power_in"))
      (node (ref "U31") (pin "8") (pinfunction "GND_8") (pintype "power_in"))
      (node (ref "U4") (pin "10") (pinfunction "GND_10") (pintype "power_in"))
      (node (ref "U4") (pin "12") (pinfunction "Q4_12") (pintype "input"))
      (node (ref "U4") (pin "16") (pinfunction "Q6_16") (pintype "input"))
      (node (ref "U4") (pin "18") (pinfunction "Q7_18") (pintype "input"))
      (node (ref "U4") (pin "3") (pinfunction "Q0_3") (pintype "input"))
      (node (ref "U4") (pin "5") (pinfunction "Q1_5") (pintype "input"))
      (node (ref "U4") (pin "7") (pinfunction "Q2_7") (pintype "input"))
      (node (ref "U4") (pin "9") (pinfunction "Q3_9") (pintype "input"))
      (node (ref "U5") (pin "10") (pinfunction "GND_10") (pintype "power_in"))
      (node (ref "U5") (pin "12") (pinfunction "Q4_12") (pintype "input"))
      (node (ref "U5") (pin "16") (pinfunction "Q6_16") (pintype "input"))
      (node (ref "U5") (pin "18") (pinfunction "Q7_18") (pintype "input"))
      (node (ref "U5") (pin "5") (pinfunction "Q1_5") (pintype "input"))
      (node (ref "U5") (pin "7") (pinfunction "Q2_7") (pintype "input"))
      (node (ref "U5") (pin "9") (pinfunction "Q3_9") (pintype "input"))
      (node (ref "U6") (pin "11") (pinfunction "I_11") (pintype "input"))
      (node (ref "U6") (pin "13") (pinfunction "I_13") (pintype "input"))
      (node (ref "U6") (pin "7") (pinfunction "GND_7") (pintype "power_in"))
      (node (ref "U7") (pin "10") (pinfunction "PRE_10") (pintype "input"))
      (node (ref "U7") (pin "11") (pinfunction "CLK_11") (pintype "input"))
      (node (ref "U7") (pin "12") (pinfunction "D_12") (pintype "input"))
      (node (ref "U7") (pin "13") (pinfunction "CLR_13") (pintype "input"))
      (node (ref "U7") (pin "7") (pinfunction "GND_7") (pintype "power_in"))
      (node (ref "U8") (pin "7") (pinfunction "GND_7") (pintype "power_in"))
      (node (ref "U9") (pin "7") (pinfunction "GND_7") (pintype "power_in"))
    )
    (net (code "166") (name "Net-(BUSAA-S)") (class "Default")
      (node (ref "BUS") (pin "33") (pinfunction "S_33") (pintype "passive"))
      (node (ref "U2") (pin "9") (pinfunction "A8_9") (pintype "bidirectional"))
    )
    (net (code "167") (name "Net-(BUSAB-S)") (class "Default")
      (node (ref "BUS") (pin "34") (pinfunction "S_34") (pintype "passive"))
      (node (ref "U2") (pin "8") (pinfunction "A7_8") (pintype "bidirectional"))
    )
    (net (code "168") (name "Net-(BUSAC-S)") (class "Default")
      (node (ref "BUS") (pin "35") (pinfunction "S_35") (pintype "passive"))
      (node (ref "U2") (pin "7") (pinfunction "A6_7") (pintype "bidirectional"))
    )
    (net (code "169") (name "Net-(BUSAD-S)") (class "Default")
      (node (ref "BUS") (pin "36") (pinfunction "S_36") (pintype "passive"))
      (node (ref "U2") (pin "6") (pinfunction "A5_6") (pintype "bidirectional"))
    )
    (net (code "170") (name "Net-(BUSAE-S)") (class "Default")
      (node (ref "BUS") (pin "37") (pinfunction "S_37") (pintype "passive"))
      (node (ref "U2") (pin "5") (pinfunction "A4_5") (pintype "bidirectional"))
    )
    (net (code "171") (name "Net-(BUSAF-S)") (class "Default")
      (node (ref "BUS") (pin "38") (pinfunction "S_38") (pintype "passive"))
      (node (ref "U2") (pin "4") (pinfunction "A3_4") (pintype "bidirectional"))
    )
    (net (code "172") (name "Net-(BUSAG-S)") (class "Default")
      (node (ref "BUS") (pin "39") (pinfunction "S_39") (pintype "passive"))
      (node (ref "U2") (pin "3") (pinfunction "A2_3") (pintype "bidirectional"))
    )
    (net (code "173") (name "Net-(BUSAI-S)") (class "Default")
      (node (ref "BUS") (pin "40") (pinfunction "S_40") (pintype "passive"))
      (node (ref "U2") (pin "2") (pinfunction "A1_2") (pintype "bidirectional"))
    )
    (net (code "174") (name "Net-(BUSAJ-S)") (class "Default")
      (node (ref "BUS") (pin "5") (pinfunction "S_5") (pintype "passive"))
      (node (ref "U3") (pin "9") (pinfunction "A8_9") (pintype "bidirectional"))
    )
    (net (code "175") (name "Net-(BUSAK-S)") (class "Default")
      (node (ref "BUS") (pin "6") (pinfunction "S_6") (pintype "passive"))
      (node (ref "U3") (pin "8") (pinfunction "A7_8") (pintype "bidirectional"))
    )
    (net (code "176") (name "Net-(BUSAL-S)") (class "Default")
      (node (ref "BUS") (pin "7") (pinfunction "S_7") (pintype "passive"))
      (node (ref "U3") (pin "6") (pinfunction "A5_6") (pintype "bidirectional"))
    )
    (net (code "177") (name "Net-(BUSAM-S)") (class "Default")
      (node (ref "BUS") (pin "8") (pinfunction "S_8") (pintype "passive"))
      (node (ref "U3") (pin "5") (pinfunction "A4_5") (pintype "bidirectional"))
    )
    (net (code "178") (name "Net-(BUSAN-S)") (class "Default")
      (node (ref "BUS") (pin "9") (pinfunction "S_9") (pintype "passive"))
      (node (ref "U3") (pin "4") (pinfunction "A3_4") (pintype "bidirectional"))
    )
    (net (code "179") (name "Net-(BUSE-S)") (class "Default")
      (node (ref "BUS") (pin "13") (pinfunction "S_13") (pintype "passive"))
      (node (ref "U3") (pin "3") (pinfunction "A2_3") (pintype "bidirectional"))
    )
    (net (code "180") (name "Net-(BUSF-S)") (class "Default")
      (node (ref "BUS") (pin "14") (pinfunction "S_14") (pintype "passive"))
      (node (ref "U3") (pin "2") (pinfunction "A1_2") (pintype "bidirectional"))
    )
    (net (code "181") (name "Net-(BUSP-S)") (class "Default")
      (node (ref "BUS") (pin "23") (pinfunction "S_23") (pintype "passive"))
      (node (ref "U1") (pin "9") (pinfunction "A8_9") (pintype "bidirectional"))
    )
    (net (code "182") (name "Net-(BUSQ-S)") (class "Default")
      (node (ref "BUS") (pin "24") (pinfunction "S_24") (pintype "passive"))
      (node (ref "U1") (pin "8") (pinfunction "A7_8") (pintype "bidirectional"))
    )
    (net (code "183") (name "Net-(BUSR-S)") (class "Default")
      (node (ref "BUS") (pin "25") (pinfunction "S_25") (pintype "passive"))
      (node (ref "U1") (pin "7") (pinfunction "A6_7") (pintype "bidirectional"))
    )
    (net (code "184") (name "Net-(BUSS-S)") (class "Default")
      (node (ref "BUS") (pin "26") (pinfunction "S_26") (pintype "passive"))
      (node (ref "U1") (pin "6") (pinfunction "A5_6") (pintype "bidirectional"))
    )
    (net (code "185") (name "Net-(BUST-S)") (class "Default")
      (node (ref "BUS") (pin "27") (pinfunction "S_27") (pintype "passive"))
      (node (ref "U1") (pin "5") (pinfunction "A4_5") (pintype "bidirectional"))
    )
    (net (code "186") (name "Net-(BUSU-S)") (class "Default")
      (node (ref "BUS") (pin "28") (pinfunction "S_28") (pintype "passive"))
      (node (ref "U1") (pin "4") (pinfunction "A3_4") (pintype "bidirectional"))
    )
    (net (code "187") (name "Net-(BUSV-S)") (class "Default")
      (node (ref "BUS") (pin "29") (pinfunction "S_29") (pintype "passive"))
      (node (ref "U1") (pin "3") (pinfunction "A2_3") (pintype "bidirectional"))
    )
    (net (code "188") (name "Net-(BUSX-S)") (class "Default")
      (node (ref "BUS") (pin "30") (pinfunction "S_30") (pintype "passive"))
      (node (ref "U1") (pin "2") (pinfunction "A1_2") (pintype "bidirectional"))
    )
    (net (code "189") (name "Net-(SV1A-S)") (class "Default")
      (node (ref "R2") (pin "2") (pinfunction "2_2") (pintype "passive"))
      (node (ref "SV1") (pin "1") (pinfunction "S_1") (pintype "passive"))
    )
    (net (code "190") (name "Net-(SV1AA-S)") (class "Default")
      (node (ref "R50") (pin "2") (pinfunction "2_2") (pintype "passive"))
      (node (ref "SV1") (pin "33") (pinfunction "S_33") (pintype "passive"))
    )
    (net (code "191") (name "Net-(SV1AB-S)") (class "Default")
      (node (ref "R51") (pin "2") (pinfunction "2_2") (pintype "passive"))
      (node (ref "SV1") (pin "34") (pinfunction "S_34") (pintype "passive"))
    )
    (net (code "192") (name "Net-(SV1AC-S)") (class "Default")
      (node (ref "R52") (pin "2") (pinfunction "2_2") (pintype "passive"))
      (node (ref "SV1") (pin "35") (pinfunction "S_35") (pintype "passive"))
    )
    (net (code "193") (name "Net-(SV1AD-S)") (class "Default")
      (node (ref "R53") (pin "2") (pinfunction "2_2") (pintype "passive"))
      (node (ref "SV1") (pin "36") (pinfunction "S_36") (pintype "passive"))
    )
    (net (code "194") (name "Net-(SV1AE-S)") (class "Default")
      (node (ref "R54") (pin "2") (pinfunction "2_2") (pintype "passive"))
      (node (ref "SV1") (pin "37") (pinfunction "S_37") (pintype "passive"))
    )
    (net (code "195") (name "Net-(SV1AF-S)") (class "Default")
      (node (ref "R55") (pin "2") (pinfunction "2_2") (pintype "passive"))
      (node (ref "SV1") (pin "38") (pinfunction "S_38") (pintype "passive"))
    )
    (net (code "196") (name "Net-(SV1AG-S)") (class "Default")
      (node (ref "R56") (pin "2") (pinfunction "2_2") (pintype "passive"))
      (node (ref "SV1") (pin "39") (pinfunction "S_39") (pintype "passive"))
    )
    (net (code "197") (name "Net-(SV1AH-S)") (class "Default")
      (node (ref "R5") (pin "2") (pinfunction "2_2") (pintype "passive"))
      (node (ref "SV1") (pin "4") (pinfunction "S_4") (pintype "passive"))
    )
    (net (code "198") (name "Net-(SV1AI-S)") (class "Default")
      (node (ref "R57") (pin "2") (pinfunction "2_2") (pintype "passive"))
      (node (ref "SV1") (pin "40") (pinfunction "S_40") (pintype "passive"))
    )
    (net (code "199") (name "Net-(SV1AJ-S)") (class "Default")
      (node (ref "R6") (pin "2") (pinfunction "2_2") (pintype "passive"))
      (node (ref "SV1") (pin "5") (pinfunction "S_5") (pintype "passive"))
    )
    (net (code "200") (name "Net-(SV1AK-S)") (class "Default")
      (node (ref "R7") (pin "2") (pinfunction "2_2") (pintype "passive"))
      (node (ref "SV1") (pin "6") (pinfunction "S_6") (pintype "passive"))
    )
    (net (code "201") (name "Net-(SV1AL-S)") (class "Default")
      (node (ref "R8") (pin "2") (pinfunction "2_2") (pintype "passive"))
      (node (ref "SV1") (pin "7") (pinfunction "S_7") (pintype "passive"))
    )
    (net (code "202") (name "Net-(SV1AM-S)") (class "Default")
      (node (ref "R9") (pin "2") (pinfunction "2_2") (pintype "passive"))
      (node (ref "SV1") (pin "8") (pinfunction "S_8") (pintype "passive"))
    )
    (net (code "203") (name "Net-(SV1AN-S)") (class "Default")
      (node (ref "R10") (pin "2") (pinfunction "2_2") (pintype "passive"))
      (node (ref "SV1") (pin "9") (pinfunction "S_9") (pintype "passive"))
    )
    (net (code "204") (name "Net-(SV1B-S)") (class "Default")
      (node (ref "R11") (pin "2") (pinfunction "2_2") (pintype "passive"))
      (node (ref "SV1") (pin "10") (pinfunction "S_10") (pintype "passive"))
    )
    (net (code "205") (name "Net-(SV1C-S)") (class "Default")
      (node (ref "R12") (pin "2") (pinfunction "2_2") (pintype "passive"))
      (node (ref "SV1") (pin "11") (pinfunction "S_11") (pintype "passive"))
    )
    (net (code "206") (name "Net-(SV1D-S)") (class "Default")
      (node (ref "R13") (pin "2") (pinfunction "2_2") (pintype "passive"))
      (node (ref "SV1") (pin "12") (pinfunction "S_12") (pintype "passive"))
    )
    (net (code "207") (name "Net-(SV1E-S)") (class "Default")
      (node (ref "R14") (pin "2") (pinfunction "2_2") (pintype "passive"))
      (node (ref "SV1") (pin "13") (pinfunction "S_13") (pintype "passive"))
    )
    (net (code "208") (name "Net-(SV1F-S)") (class "Default")
      (node (ref "R15") (pin "2") (pinfunction "2_2") (pintype "passive"))
      (node (ref "SV1") (pin "14") (pinfunction "S_14") (pintype "passive"))
    )
    (net (code "209") (name "Net-(SV1G-S)") (class "Default")
      (node (ref "R16") (pin "2") (pinfunction "2_2") (pintype "passive"))
      (node (ref "SV1") (pin "15") (pinfunction "S_15") (pintype "passive"))
    )
    (net (code "210") (name "Net-(SV1H-S)") (class "Default")
      (node (ref "R17") (pin "2") (pinfunction "2_2") (pintype "passive"))
      (node (ref "SV1") (pin "16") (pinfunction "S_16") (pintype "passive"))
    )
    (net (code "211") (name "Net-(SV1I-S)") (class "Default")
      (node (ref "R18") (pin "2") (pinfunction "2_2") (pintype "passive"))
      (node (ref "SV1") (pin "17") (pinfunction "S_17") (pintype "passive"))
    )
    (net (code "212") (name "Net-(SV1J-S)") (class "Default")
      (node (ref "R19") (pin "2") (pinfunction "2_2") (pintype "passive"))
      (node (ref "SV1") (pin "18") (pinfunction "S_18") (pintype "passive"))
    )
    (net (code "213") (name "Net-(SV1K-S)") (class "Default")
      (node (ref "R20") (pin "2") (pinfunction "2_2") (pintype "passive"))
      (node (ref "SV1") (pin "19") (pinfunction "S_19") (pintype "passive"))
    )
    (net (code "214") (name "Net-(SV1L-S)") (class "Default")
      (node (ref "R3") (pin "2") (pinfunction "2_2") (pintype "passive"))
      (node (ref "SV1") (pin "2") (pinfunction "S_2") (pintype "passive"))
    )
    (net (code "215") (name "Net-(SV1M-S)") (class "Default")
      (node (ref "R21") (pin "2") (pinfunction "2_2") (pintype "passive"))
      (node (ref "SV1") (pin "20") (pinfunction "S_20") (pintype "passive"))
    )
    (net (code "216") (name "Net-(SV1N-S)") (class "Default")
      (node (ref "R22") (pin "2") (pinfunction "2_2") (pintype "passive"))
      (node (ref "SV1") (pin "21") (pinfunction "S_21") (pintype "passive"))
    )
    (net (code "217") (name "Net-(SV1O-S)") (class "Default")
      (node (ref "R23") (pin "2") (pinfunction "2_2") (pintype "passive"))
      (node (ref "SV1") (pin "22") (pinfunction "S_22") (pintype "passive"))
    )
    (net (code "218") (name "Net-(SV1P-S)") (class "Default")
      (node (ref "R24") (pin "2") (pinfunction "2_2") (pintype "passive"))
      (node (ref "SV1") (pin "23") (pinfunction "S_23") (pintype "passive"))
    )
    (net (code "219") (name "Net-(SV1Q-S)") (class "Default")
      (node (ref "R25") (pin "2") (pinfunction "2_2") (pintype "passive"))
      (node (ref "SV1") (pin "24") (pinfunction "S_24") (pintype "passive"))
    )
    (net (code "220") (name "Net-(SV1R-S)") (class "Default")
      (node (ref "R42") (pin "2") (pinfunction "2_2") (pintype "passive"))
      (node (ref "SV1") (pin "25") (pinfunction "S_25") (pintype "passive"))
    )
    (net (code "221") (name "Net-(SV1S-S)") (class "Default")
      (node (ref "R43") (pin "2") (pinfunction "2_2") (pintype "passive"))
      (node (ref "SV1") (pin "26") (pinfunction "S_26") (pintype "passive"))
    )
    (net (code "222") (name "Net-(SV1T-S)") (class "Default")
      (node (ref "R44") (pin "2") (pinfunction "2_2") (pintype "passive"))
      (node (ref "SV1") (pin "27") (pinfunction "S_27") (pintype "passive"))
    )
    (net (code "223") (name "Net-(SV1U-S)") (class "Default")
      (node (ref "R45") (pin "2") (pinfunction "2_2") (pintype "passive"))
      (node (ref "SV1") (pin "28") (pinfunction "S_28") (pintype "passive"))
    )
    (net (code "224") (name "Net-(SV1V-S)") (class "Default")
      (node (ref "R46") (pin "2") (pinfunction "2_2") (pintype "passive"))
      (node (ref "SV1") (pin "29") (pinfunction "S_29") (pintype "passive"))
    )
    (net (code "225") (name "Net-(SV1W-S)") (class "Default")
      (node (ref "R4") (pin "2") (pinfunction "2_2") (pintype "passive"))
      (node (ref "SV1") (pin "3") (pinfunction "S_3") (pintype "passive"))
    )
    (net (code "226") (name "Net-(SV1X-S)") (class "Default")
      (node (ref "R47") (pin "2") (pinfunction "2_2") (pintype "passive"))
      (node (ref "SV1") (pin "30") (pinfunction "S_30") (pintype "passive"))
    )
    (net (code "227") (name "Net-(SV1Y-S)") (class "Default")
      (node (ref "R48") (pin "2") (pinfunction "2_2") (pintype "passive"))
      (node (ref "SV1") (pin "31") (pinfunction "S_31") (pintype "passive"))
    )
    (net (code "228") (name "Net-(SV1Z-S)") (class "Default")
      (node (ref "R49") (pin "2") (pinfunction "2_2") (pintype "passive"))
      (node (ref "SV1") (pin "32") (pinfunction "S_32") (pintype "passive"))
    )
    (net (code "229") (name "Net-(SV2A-S)") (class "Default")
      (node (ref "R74") (pin "2") (pinfunction "2_2") (pintype "passive"))
      (node (ref "SV2") (pin "1") (pinfunction "S_1") (pintype "passive"))
    )
    (net (code "230") (name "Net-(SV2AA-S)") (class "Default")
      (node (ref "R122") (pin "2") (pinfunction "2_2") (pintype "passive"))
      (node (ref "SV2") (pin "33") (pinfunction "S_33") (pintype "passive"))
    )
    (net (code "231") (name "Net-(SV2AB-S)") (class "Default")
      (node (ref "R123") (pin "2") (pinfunction "2_2") (pintype "passive"))
      (node (ref "SV2") (pin "34") (pinfunction "S_34") (pintype "passive"))
    )
    (net (code "232") (name "Net-(SV2AC-S)") (class "Default")
      (node (ref "R124") (pin "2") (pinfunction "2_2") (pintype "passive"))
      (node (ref "SV2") (pin "35") (pinfunction "S_35") (pintype "passive"))
    )
    (net (code "233") (name "Net-(SV2AD-S)") (class "Default")
      (node (ref "R125") (pin "2") (pinfunction "2_2") (pintype "passive"))
      (node (ref "SV2") (pin "36") (pinfunction "S_36") (pintype "passive"))
    )
    (net (code "234") (name "Net-(SV2AE-S)") (class "Default")
      (node (ref "R126") (pin "2") (pinfunction "2_2") (pintype "passive"))
      (node (ref "SV2") (pin "37") (pinfunction "S_37") (pintype "passive"))
    )
    (net (code "235") (name "Net-(SV2AF-S)") (class "Default")
      (node (ref "R127") (pin "2") (pinfunction "2_2") (pintype "passive"))
      (node (ref "SV2") (pin "38") (pinfunction "S_38") (pintype "passive"))
    )
    (net (code "236") (name "Net-(SV2AG-S)") (class "Default")
      (node (ref "R128") (pin "2") (pinfunction "2_2") (pintype "passive"))
      (node (ref "SV2") (pin "39") (pinfunction "S_39") (pintype "passive"))
    )
    (net (code "237") (name "Net-(SV2AH-S)") (class "Default")
      (node (ref "R77") (pin "2") (pinfunction "2_2") (pintype "passive"))
      (node (ref "SV2") (pin "4") (pinfunction "S_4") (pintype "passive"))
    )
    (net (code "238") (name "Net-(SV2AI-S)") (class "Default")
      (node (ref "R129") (pin "2") (pinfunction "2_2") (pintype "passive"))
      (node (ref "SV2") (pin "40") (pinfunction "S_40") (pintype "passive"))
    )
    (net (code "239") (name "Net-(SV2AJ-S)") (class "Default")
      (node (ref "R78") (pin "2") (pinfunction "2_2") (pintype "passive"))
      (node (ref "SV2") (pin "5") (pinfunction "S_5") (pintype "passive"))
    )
    (net (code "240") (name "Net-(SV2AK-S)") (class "Default")
      (node (ref "R79") (pin "2") (pinfunction "2_2") (pintype "passive"))
      (node (ref "SV2") (pin "6") (pinfunction "S_6") (pintype "passive"))
    )
    (net (code "241") (name "Net-(SV2AL-S)") (class "Default")
      (node (ref "R80") (pin "2") (pinfunction "2_2") (pintype "passive"))
      (node (ref "SV2") (pin "7") (pinfunction "S_7") (pintype "passive"))
    )
    (net (code "242") (name "Net-(SV2AM-S)") (class "Default")
      (node (ref "R81") (pin "2") (pinfunction "2_2") (pintype "passive"))
      (node (ref "SV2") (pin "8") (pinfunction "S_8") (pintype "passive"))
    )
    (net (code "243") (name "Net-(SV2AN-S)") (class "Default")
      (node (ref "R82") (pin "2") (pinfunction "2_2") (pintype "passive"))
      (node (ref "SV2") (pin "9") (pinfunction "S_9") (pintype "passive"))
    )
    (net (code "244") (name "Net-(SV2B-S)") (class "Default")
      (node (ref "R83") (pin "2") (pinfunction "2_2") (pintype "passive"))
      (node (ref "SV2") (pin "10") (pinfunction "S_10") (pintype "passive"))
    )
    (net (code "245") (name "Net-(SV2C-S)") (class "Default")
      (node (ref "R84") (pin "2") (pinfunction "2_2") (pintype "passive"))
      (node (ref "SV2") (pin "11") (pinfunction "S_11") (pintype "passive"))
    )
    (net (code "246") (name "Net-(SV2D-S)") (class "Default")
      (node (ref "R85") (pin "2") (pinfunction "2_2") (pintype "passive"))
      (node (ref "SV2") (pin "12") (pinfunction "S_12") (pintype "passive"))
    )
    (net (code "247") (name "Net-(SV2E-S)") (class "Default")
      (node (ref "R86") (pin "2") (pinfunction "2_2") (pintype "passive"))
      (node (ref "SV2") (pin "13") (pinfunction "S_13") (pintype "passive"))
    )
    (net (code "248") (name "Net-(SV2F-S)") (class "Default")
      (node (ref "R87") (pin "2") (pinfunction "2_2") (pintype "passive"))
      (node (ref "SV2") (pin "14") (pinfunction "S_14") (pintype "passive"))
    )
    (net (code "249") (name "Net-(SV2G-S)") (class "Default")
      (node (ref "R88") (pin "2") (pinfunction "2_2") (pintype "passive"))
      (node (ref "SV2") (pin "15") (pinfunction "S_15") (pintype "passive"))
    )
    (net (code "250") (name "Net-(SV2H-S)") (class "Default")
      (node (ref "R89") (pin "2") (pinfunction "2_2") (pintype "passive"))
      (node (ref "SV2") (pin "16") (pinfunction "S_16") (pintype "passive"))
    )
    (net (code "251") (name "Net-(SV2I-S)") (class "Default")
      (node (ref "R106") (pin "2") (pinfunction "2_2") (pintype "passive"))
      (node (ref "SV2") (pin "17") (pinfunction "S_17") (pintype "passive"))
    )
    (net (code "252") (name "Net-(SV2J-S)") (class "Default")
      (node (ref "R107") (pin "2") (pinfunction "2_2") (pintype "passive"))
      (node (ref "SV2") (pin "18") (pinfunction "S_18") (pintype "passive"))
    )
    (net (code "253") (name "Net-(SV2K-S)") (class "Default")
      (node (ref "R108") (pin "2") (pinfunction "2_2") (pintype "passive"))
      (node (ref "SV2") (pin "19") (pinfunction "S_19") (pintype "passive"))
    )
    (net (code "254") (name "Net-(SV2L-S)") (class "Default")
      (node (ref "R75") (pin "2") (pinfunction "2_2") (pintype "passive"))
      (node (ref "SV2") (pin "2") (pinfunction "S_2") (pintype "passive"))
    )
    (net (code "255") (name "Net-(SV2M-S)") (class "Default")
      (node (ref "R109") (pin "2") (pinfunction "2_2") (pintype "passive"))
      (node (ref "SV2") (pin "20") (pinfunction "S_20") (pintype "passive"))
    )
    (net (code "256") (name "Net-(SV2N-S)") (class "Default")
      (node (ref "R110") (pin "2") (pinfunction "2_2") (pintype "passive"))
      (node (ref "SV2") (pin "21") (pinfunction "S_21") (pintype "passive"))
    )
    (net (code "257") (name "Net-(SV2O-S)") (class "Default")
      (node (ref "R111") (pin "2") (pinfunction "2_2") (pintype "passive"))
      (node (ref "SV2") (pin "22") (pinfunction "S_22") (pintype "passive"))
    )
    (net (code "258") (name "Net-(SV2P-S)") (class "Default")
      (node (ref "R112") (pin "2") (pinfunction "2_2") (pintype "passive"))
      (node (ref "SV2") (pin "23") (pinfunction "S_23") (pintype "passive"))
    )
    (net (code "259") (name "Net-(SV2Q-S)") (class "Default")
      (node (ref "R113") (pin "2") (pinfunction "2_2") (pintype "passive"))
      (node (ref "SV2") (pin "24") (pinfunction "S_24") (pintype "passive"))
    )
    (net (code "260") (name "Net-(SV2R-S)") (class "Default")
      (node (ref "R114") (pin "2") (pinfunction "2_2") (pintype "passive"))
      (node (ref "SV2") (pin "25") (pinfunction "S_25") (pintype "passive"))
    )
    (net (code "261") (name "Net-(SV2S-S)") (class "Default")
      (node (ref "R115") (pin "2") (pinfunction "2_2") (pintype "passive"))
      (node (ref "SV2") (pin "26") (pinfunction "S_26") (pintype "passive"))
    )
    (net (code "262") (name "Net-(SV2T-S)") (class "Default")
      (node (ref "R116") (pin "2") (pinfunction "2_2") (pintype "passive"))
      (node (ref "SV2") (pin "27") (pinfunction "S_27") (pintype "passive"))
    )
    (net (code "263") (name "Net-(SV2U-S)") (class "Default")
      (node (ref "R117") (pin "2") (pinfunction "2_2") (pintype "passive"))
      (node (ref "SV2") (pin "28") (pinfunction "S_28") (pintype "passive"))
    )
    (net (code "264") (name "Net-(SV2V-S)") (class "Default")
      (node (ref "R118") (pin "2") (pinfunction "2_2") (pintype "passive"))
      (node (ref "SV2") (pin "29") (pinfunction "S_29") (pintype "passive"))
    )
    (net (code "265") (name "Net-(SV2W-S)") (class "Default")
      (node (ref "R76") (pin "2") (pinfunction "2_2") (pintype "passive"))
      (node (ref "SV2") (pin "3") (pinfunction "S_3") (pintype "passive"))
    )
    (net (code "266") (name "Net-(SV2X-S)") (class "Default")
      (node (ref "R119") (pin "2") (pinfunction "2_2") (pintype "passive"))
      (node (ref "SV2") (pin "30") (pinfunction "S_30") (pintype "passive"))
    )
    (net (code "267") (name "Net-(SV2Y-S)") (class "Default")
      (node (ref "R120") (pin "2") (pinfunction "2_2") (pintype "passive"))
      (node (ref "SV2") (pin "31") (pinfunction "S_31") (pintype "passive"))
    )
    (net (code "268") (name "Net-(SV2Z-S)") (class "Default")
      (node (ref "R121") (pin "2") (pinfunction "2_2") (pintype "passive"))
      (node (ref "SV2") (pin "32") (pinfunction "S_32") (pintype "passive"))
    )
    (net (code "269") (name "Net-(SV3A-S)") (class "Default")
      (node (ref "R26") (pin "2") (pinfunction "2_2") (pintype "passive"))
      (node (ref "SV3") (pin "1") (pinfunction "S_1") (pintype "passive"))
    )
    (net (code "270") (name "Net-(SV3AA-S)") (class "Default")
      (node (ref "R66") (pin "2") (pinfunction "2_2") (pintype "passive"))
      (node (ref "SV3") (pin "33") (pinfunction "S_33") (pintype "passive"))
    )
    (net (code "271") (name "Net-(SV3AB-S)") (class "Default")
      (node (ref "R67") (pin "2") (pinfunction "2_2") (pintype "passive"))
      (node (ref "SV3") (pin "34") (pinfunction "S_34") (pintype "passive"))
    )
    (net (code "272") (name "Net-(SV3AC-S)") (class "Default")
      (node (ref "R68") (pin "2") (pinfunction "2_2") (pintype "passive"))
      (node (ref "SV3") (pin "35") (pinfunction "S_35") (pintype "passive"))
    )
    (net (code "273") (name "Net-(SV3AD-S)") (class "Default")
      (node (ref "R69") (pin "2") (pinfunction "2_2") (pintype "passive"))
      (node (ref "SV3") (pin "36") (pinfunction "S_36") (pintype "passive"))
    )
    (net (code "274") (name "Net-(SV3AE-S)") (class "Default")
      (node (ref "R70") (pin "2") (pinfunction "2_2") (pintype "passive"))
      (node (ref "SV3") (pin "37") (pinfunction "S_37") (pintype "passive"))
    )
    (net (code "275") (name "Net-(SV3AF-S)") (class "Default")
      (node (ref "R71") (pin "2") (pinfunction "2_2") (pintype "passive"))
      (node (ref "SV3") (pin "38") (pinfunction "S_38") (pintype "passive"))
    )
    (net (code "276") (name "Net-(SV3AG-S)") (class "Default")
      (node (ref "R72") (pin "2") (pinfunction "2_2") (pintype "passive"))
      (node (ref "SV3") (pin "39") (pinfunction "S_39") (pintype "passive"))
    )
    (net (code "277") (name "Net-(SV3AH-S)") (class "Default")
      (node (ref "R29") (pin "2") (pinfunction "2_2") (pintype "passive"))
      (node (ref "SV3") (pin "4") (pinfunction "S_4") (pintype "passive"))
    )
    (net (code "278") (name "Net-(SV3AI-S)") (class "Default")
      (node (ref "R73") (pin "2") (pinfunction "2_2") (pintype "passive"))
      (node (ref "SV3") (pin "40") (pinfunction "S_40") (pintype "passive"))
    )
    (net (code "279") (name "Net-(SV3AJ-S)") (class "Default")
      (node (ref "R30") (pin "2") (pinfunction "2_2") (pintype "passive"))
      (node (ref "SV3") (pin "5") (pinfunction "S_5") (pintype "passive"))
    )
    (net (code "280") (name "Net-(SV3AK-S)") (class "Default")
      (node (ref "R31") (pin "2") (pinfunction "2_2") (pintype "passive"))
      (node (ref "SV3") (pin "6") (pinfunction "S_6") (pintype "passive"))
    )
    (net (code "281") (name "Net-(SV3AL-S)") (class "Default")
      (node (ref "R32") (pin "2") (pinfunction "2_2") (pintype "passive"))
      (node (ref "SV3") (pin "7") (pinfunction "S_7") (pintype "passive"))
    )
    (net (code "282") (name "Net-(SV3AM-S)") (class "Default")
      (node (ref "R33") (pin "2") (pinfunction "2_2") (pintype "passive"))
      (node (ref "SV3") (pin "8") (pinfunction "S_8") (pintype "passive"))
    )
    (net (code "283") (name "Net-(SV3AN-S)") (class "Default")
      (node (ref "R34") (pin "2") (pinfunction "2_2") (pintype "passive"))
      (node (ref "SV3") (pin "9") (pinfunction "S_9") (pintype "passive"))
    )
    (net (code "284") (name "Net-(SV3B-S)") (class "Default")
      (node (ref "R35") (pin "2") (pinfunction "2_2") (pintype "passive"))
      (node (ref "SV3") (pin "10") (pinfunction "S_10") (pintype "passive"))
    )
    (net (code "285") (name "Net-(SV3C-S)") (class "Default")
      (node (ref "R36") (pin "2") (pinfunction "2_2") (pintype "passive"))
      (node (ref "SV3") (pin "11") (pinfunction "S_11") (pintype "passive"))
    )
    (net (code "286") (name "Net-(SV3D-S)") (class "Default")
      (node (ref "R37") (pin "2") (pinfunction "2_2") (pintype "passive"))
      (node (ref "SV3") (pin "12") (pinfunction "S_12") (pintype "passive"))
    )
    (net (code "287") (name "Net-(SV3E-S)") (class "Default")
      (node (ref "R38") (pin "2") (pinfunction "2_2") (pintype "passive"))
      (node (ref "SV3") (pin "13") (pinfunction "S_13") (pintype "passive"))
    )
    (net (code "288") (name "Net-(SV3F-S)") (class "Default")
      (node (ref "R39") (pin "2") (pinfunction "2_2") (pintype "passive"))
      (node (ref "SV3") (pin "14") (pinfunction "S_14") (pintype "passive"))
    )
    (net (code "289") (name "Net-(SV3G-S)") (class "Default")
      (node (ref "R40") (pin "2") (pinfunction "2_2") (pintype "passive"))
      (node (ref "SV3") (pin "15") (pinfunction "S_15") (pintype "passive"))
    )
    (net (code "290") (name "Net-(SV3H-S)") (class "Default")
      (node (ref "R41") (pin "2") (pinfunction "2_2") (pintype "passive"))
      (node (ref "SV3") (pin "16") (pinfunction "S_16") (pintype "passive"))
    )
    (net (code "291") (name "Net-(SV3L-S)") (class "Default")
      (node (ref "R27") (pin "2") (pinfunction "2_2") (pintype "passive"))
      (node (ref "SV3") (pin "2") (pinfunction "S_2") (pintype "passive"))
    )
    (net (code "292") (name "Net-(SV3R-S)") (class "Default")
      (node (ref "R58") (pin "2") (pinfunction "2_2") (pintype "passive"))
      (node (ref "SV3") (pin "25") (pinfunction "S_25") (pintype "passive"))
    )
    (net (code "293") (name "Net-(SV3S-S)") (class "Default")
      (node (ref "R59") (pin "2") (pinfunction "2_2") (pintype "passive"))
      (node (ref "SV3") (pin "26") (pinfunction "S_26") (pintype "passive"))
    )
    (net (code "294") (name "Net-(SV3T-S)") (class "Default")
      (node (ref "R60") (pin "2") (pinfunction "2_2") (pintype "passive"))
      (node (ref "SV3") (pin "27") (pinfunction "S_27") (pintype "passive"))
    )
    (net (code "295") (name "Net-(SV3U-S)") (class "Default")
      (node (ref "R61") (pin "2") (pinfunction "2_2") (pintype "passive"))
      (node (ref "SV3") (pin "28") (pinfunction "S_28") (pintype "passive"))
    )
    (net (code "296") (name "Net-(SV3V-S)") (class "Default")
      (node (ref "R62") (pin "2") (pinfunction "2_2") (pintype "passive"))
      (node (ref "SV3") (pin "29") (pinfunction "S_29") (pintype "passive"))
    )
    (net (code "297") (name "Net-(SV3W-S)") (class "Default")
      (node (ref "R28") (pin "2") (pinfunction "2_2") (pintype "passive"))
      (node (ref "SV3") (pin "3") (pinfunction "S_3") (pintype "passive"))
    )
    (net (code "298") (name "Net-(SV3X-S)") (class "Default")
      (node (ref "R63") (pin "2") (pinfunction "2_2") (pintype "passive"))
      (node (ref "SV3") (pin "30") (pinfunction "S_30") (pintype "passive"))
    )
    (net (code "299") (name "Net-(SV3Y-S)") (class "Default")
      (node (ref "R64") (pin "2") (pinfunction "2_2") (pintype "passive"))
      (node (ref "SV3") (pin "31") (pinfunction "S_31") (pintype "passive"))
    )
    (net (code "300") (name "Net-(SV3Z-S)") (class "Default")
      (node (ref "R65") (pin "2") (pinfunction "2_2") (pintype "passive"))
      (node (ref "SV3") (pin "32") (pinfunction "S_32") (pintype "passive"))
    )
    (net (code "301") (name "Net-(SV4A-S)") (class "Default")
      (node (ref "R90") (pin "2") (pinfunction "2_2") (pintype "passive"))
      (node (ref "SV4") (pin "1") (pinfunction "S_1") (pintype "passive"))
    )
    (net (code "302") (name "Net-(SV4AH-S)") (class "Default")
      (node (ref "R93") (pin "2") (pinfunction "2_2") (pintype "passive"))
      (node (ref "SV4") (pin "4") (pinfunction "S_4") (pintype "passive"))
    )
    (net (code "303") (name "Net-(SV4AJ-S)") (class "Default")
      (node (ref "R94") (pin "2") (pinfunction "2_2") (pintype "passive"))
      (node (ref "SV4") (pin "5") (pinfunction "S_5") (pintype "passive"))
    )
    (net (code "304") (name "Net-(SV4AK-S)") (class "Default")
      (node (ref "R95") (pin "2") (pinfunction "2_2") (pintype "passive"))
      (node (ref "SV4") (pin "6") (pinfunction "S_6") (pintype "passive"))
    )
    (net (code "305") (name "Net-(SV4AL-S)") (class "Default")
      (node (ref "R96") (pin "2") (pinfunction "2_2") (pintype "passive"))
      (node (ref "SV4") (pin "7") (pinfunction "S_7") (pintype "passive"))
    )
    (net (code "306") (name "Net-(SV4AM-S)") (class "Default")
      (node (ref "R97") (pin "2") (pinfunction "2_2") (pintype "passive"))
      (node (ref "SV4") (pin "8") (pinfunction "S_8") (pintype "passive"))
    )
    (net (code "307") (name "Net-(SV4AN-S)") (class "Default")
      (node (ref "R98") (pin "2") (pinfunction "2_2") (pintype "passive"))
      (node (ref "SV4") (pin "9") (pinfunction "S_9") (pintype "passive"))
    )
    (net (code "308") (name "Net-(SV4B-S)") (class "Default")
      (node (ref "R99") (pin "2") (pinfunction "2_2") (pintype "passive"))
      (node (ref "SV4") (pin "10") (pinfunction "S_10") (pintype "passive"))
    )
    (net (code "309") (name "Net-(SV4C-S)") (class "Default")
      (node (ref "R100") (pin "2") (pinfunction "2_2") (pintype "passive"))
      (node (ref "SV4") (pin "11") (pinfunction "S_11") (pintype "passive"))
    )
    (net (code "310") (name "Net-(SV4D-S)") (class "Default")
      (node (ref "R101") (pin "2") (pinfunction "2_2") (pintype "passive"))
      (node (ref "SV4") (pin "12") (pinfunction "S_12") (pintype "passive"))
    )
    (net (code "311") (name "Net-(SV4E-S)") (class "Default")
      (node (ref "R102") (pin "2") (pinfunction "2_2") (pintype "passive"))
      (node (ref "SV4") (pin "13") (pinfunction "S_13") (pintype "passive"))
    )
    (net (code "312") (name "Net-(SV4F-S)") (class "Default")
      (node (ref "R103") (pin "2") (pinfunction "2_2") (pintype "passive"))
      (node (ref "SV4") (pin "14") (pinfunction "S_14") (pintype "passive"))
    )
    (net (code "313") (name "Net-(SV4G-S)") (class "Default")
      (node (ref "R104") (pin "2") (pinfunction "2_2") (pintype "passive"))
      (node (ref "SV4") (pin "15") (pinfunction "S_15") (pintype "passive"))
    )
    (net (code "314") (name "Net-(SV4H-S)") (class "Default")
      (node (ref "R105") (pin "2") (pinfunction "2_2") (pintype "passive"))
      (node (ref "SV4") (pin "16") (pinfunction "S_16") (pintype "passive"))
    )
    (net (code "315") (name "Net-(SV4I-S)") (class "Default")
      (node (ref "R130") (pin "2") (pinfunction "2_2") (pintype "passive"))
      (node (ref "SV4") (pin "17") (pinfunction "S_17") (pintype "passive"))
    )
    (net (code "316") (name "Net-(SV4J-S)") (class "Default")
      (node (ref "R131") (pin "2") (pinfunction "2_2") (pintype "passive"))
      (node (ref "SV4") (pin "18") (pinfunction "S_18") (pintype "passive"))
    )
    (net (code "317") (name "Net-(SV4K-S)") (class "Default")
      (node (ref "R132") (pin "2") (pinfunction "2_2") (pintype "passive"))
      (node (ref "SV4") (pin "19") (pinfunction "S_19") (pintype "passive"))
    )
    (net (code "318") (name "Net-(SV4L-S)") (class "Default")
      (node (ref "R91") (pin "2") (pinfunction "2_2") (pintype "passive"))
      (node (ref "SV4") (pin "2") (pinfunction "S_2") (pintype "passive"))
    )
    (net (code "319") (name "Net-(SV4M-S)") (class "Default")
      (node (ref "R133") (pin "2") (pinfunction "2_2") (pintype "passive"))
      (node (ref "SV4") (pin "20") (pinfunction "S_20") (pintype "passive"))
    )
    (net (code "320") (name "Net-(SV4N-S)") (class "Default")
      (node (ref "R134") (pin "2") (pinfunction "2_2") (pintype "passive"))
      (node (ref "SV4") (pin "21") (pinfunction "S_21") (pintype "passive"))
    )
    (net (code "321") (name "Net-(SV4O-S)") (class "Default")
      (node (ref "R135") (pin "2") (pinfunction "2_2") (pintype "passive"))
      (node (ref "SV4") (pin "22") (pinfunction "S_22") (pintype "passive"))
    )
    (net (code "322") (name "Net-(SV4P-S)") (class "Default")
      (node (ref "R136") (pin "2") (pinfunction "2_2") (pintype "passive"))
      (node (ref "SV4") (pin "23") (pinfunction "S_23") (pintype "passive"))
    )
    (net (code "323") (name "Net-(SV4Q-S)") (class "Default")
      (node (ref "R137") (pin "2") (pinfunction "2_2") (pintype "passive"))
      (node (ref "SV4") (pin "24") (pinfunction "S_24") (pintype "passive"))
    )
    (net (code "324") (name "Net-(SV4W-S)") (class "Default")
      (node (ref "R92") (pin "2") (pinfunction "2_2") (pintype "passive"))
      (node (ref "SV4") (pin "3") (pinfunction "S_3") (pintype "passive"))
    )
    (net (code "325") (name "Net-(U6A-O)") (class "Default")
      (node (ref "U6") (pin "2") (pinfunction "O_2") (pintype "output"))
      (node (ref "U8") (pin "10") (pinfunction "I1_10") (pintype "input"))
    )
    (net (code "326") (name "Net-(U6B-O)") (class "Default")
      (node (ref "U6") (pin "4") (pinfunction "O_4") (pintype "output"))
      (node (ref "U8") (pin "12") (pinfunction "I0_12") (pintype "input"))
    )
    (net (code "327") (name "Net-(U6D-I)") (class "Default")
      (node (ref "U6") (pin "9") (pinfunction "I_9") (pintype "input"))
      (node (ref "U8") (pin "8") (pinfunction "O_8") (pintype "output"))
    )
    (net (code "328") (name "Net-(U6D-O)") (class "Default")
      (node (ref "U6") (pin "8") (pinfunction "O_8") (pintype "output"))
      (node (ref "U8") (pin "2") (pinfunction "I1_2") (pintype "input"))
    )
    (net (code "329") (name "Net-(U7A-CLR)") (class "Default")
      (node (ref "U7") (pin "1") (pinfunction "CLR_1") (pintype "input"))
      (node (ref "U8") (pin "3") (pinfunction "O_3") (pintype "output"))
    )
    (net (code "330") (name "Net-(U7A-Q)") (class "Default")
      (node (ref "U7") (pin "5") (pinfunction "Q_5") (pintype "output"))
      (node (ref "U8") (pin "5") (pinfunction "I1_5") (pintype "input"))
    )
    (net (code "331") (name "Net-(U7A-~{Q})") (class "Default")
      (node (ref "U7") (pin "6") (pinfunction "~{Q}_6") (pintype "output"))
      (node (ref "U9") (pin "2") (pinfunction "CLR_2") (pintype "input"))
    )
    (net (code "332") (name "Net-(U8C-I0)") (class "Default")
      (node (ref "U8") (pin "9") (pinfunction "I0_9") (pintype "input"))
      (node (ref "U9") (pin "6") (pinfunction "QD_6") (pintype "output"))
    )
    (net (code "333") (name "Net-(U10A-O)") (class "Default")
      (node (ref "U10") (pin "3") (pinfunction "O_3") (pintype "output"))
      (node (ref "U4") (pin "1") (pinfunction "G_1") (pintype "input"))
      (node (ref "U5") (pin "1") (pinfunction "G_1") (pintype "input"))
    )
    (net (code "334") (name "Net-(U10B-I0)") (class "Default")
      (node (ref "U10") (pin "4") (pinfunction "I0_4") (pintype "input"))
      (node (ref "U8") (pin "11") (pinfunction "O_11") (pintype "output"))
    )
    (net (code "335") (name "Net-(U10B-I1)") (class "Default")
      (node (ref "U10") (pin "5") (pinfunction "I1_5") (pintype "input"))
      (node (ref "U15") (pin "11") (pinfunction "SCK_11") (pintype "input"))
      (node (ref "U16") (pin "11") (pinfunction "SCK_11") (pintype "input"))
      (node (ref "U17") (pin "11") (pinfunction "SCK_11") (pintype "input"))
      (node (ref "U18") (pin "11") (pinfunction "SCK_11") (pintype "input"))
      (node (ref "U19") (pin "11") (pinfunction "SCK_11") (pintype "input"))
      (node (ref "U20") (pin "11") (pinfunction "SCK_11") (pintype "input"))
      (node (ref "U21") (pin "11") (pinfunction "SCK_11") (pintype "input"))
      (node (ref "U22") (pin "11") (pinfunction "SCK_11") (pintype "input"))
      (node (ref "U23") (pin "11") (pinfunction "SCK_11") (pintype "input"))
      (node (ref "U24") (pin "11") (pinfunction "SCK_11") (pintype "input"))
      (node (ref "U25") (pin "11") (pinfunction "SCK_11") (pintype "input"))
      (node (ref "U26") (pin "11") (pinfunction "SCK_11") (pintype "input"))
      (node (ref "U27") (pin "11") (pinfunction "SCK_11") (pintype "input"))
      (node (ref "U28") (pin "11") (pinfunction "SCK_11") (pintype "input"))
      (node (ref "U29") (pin "11") (pinfunction "SCK_11") (pintype "input"))
      (node (ref "U30") (pin "11") (pinfunction "SCK_11") (pintype "input"))
      (node (ref "U31") (pin "11") (pinfunction "SCK_11") (pintype "input"))
      (node (ref "U6") (pin "1") (pinfunction "I_1") (pintype "input"))
      (node (ref "U8") (pin "6") (pinfunction "O_6") (pintype "output"))
      (node (ref "U9") (pin "1") (pinfunction "A_1") (pintype "input"))
    )
    (net (code "336") (name "Net-(U10B-O)") (class "Default")
      (node (ref "U10") (pin "6") (pinfunction "O_6") (pintype "output"))
      (node (ref "U11") (pin "7") (pinfunction "CLK_7") (pintype "input"))
    )
    (net (code "337") (name "Net-(U11A-QH)") (class "Default")
      (node (ref "U11") (pin "13") (pinfunction "QH_13") (pintype "output"))
      (node (ref "U15") (pin "14") (pinfunction "SER_14") (pintype "input"))
    )
    (net (code "338") (name "Net-(U11A-SH{slash}~{LD})") (class "Default")
      (node (ref "U11") (pin "15") (pinfunction "SH/~{LD}_15") (pintype "input"))
      (node (ref "U4") (pin "19") (pinfunction "P=Q_19") (pintype "output"))
      (node (ref "U6") (pin "3") (pinfunction "I_3") (pintype "input"))
      (node (ref "U7") (pin "3") (pinfunction "CLK_3") (pintype "input"))
    )
    (net (code "339") (name "Net-(U12A-I1)") (class "Default")
      (node (ref "U12") (pin "2") (pinfunction "I1_2") (pintype "input"))
      (node (ref "U12") (pin "5") (pinfunction "I1_5") (pintype "input"))
      (node (ref "U5") (pin "19") (pinfunction "P=Q_19") (pintype "output"))
    )
    (net (code "340") (name "Net-(U12A-O)") (class "Default")
      (node (ref "U12") (pin "3") (pinfunction "O_3") (pintype "output"))
      (node (ref "U15") (pin "12") (pinfunction "RCK_12") (pintype "input"))
      (node (ref "U16") (pin "12") (pinfunction "RCK_12") (pintype "input"))
      (node (ref "U17") (pin "12") (pinfunction "RCK_12") (pintype "input"))
      (node (ref "U18") (pin "12") (pinfunction "RCK_12") (pintype "input"))
      (node (ref "U19") (pin "12") (pinfunction "RCK_12") (pintype "input"))
      (node (ref "U20") (pin "12") (pinfunction "RCK_12") (pintype "input"))
      (node (ref "U21") (pin "12") (pinfunction "RCK_12") (pintype "input"))
      (node (ref "U22") (pin "12") (pinfunction "RCK_12") (pintype "input"))
      (node (ref "U23") (pin "12") (pinfunction "RCK_12") (pintype "input"))
      (node (ref "U24") (pin "12") (pinfunction "RCK_12") (pintype "input"))
      (node (ref "U25") (pin "12") (pinfunction "RCK_12") (pintype "input"))
      (node (ref "U26") (pin "12") (pinfunction "RCK_12") (pintype "input"))
      (node (ref "U27") (pin "12") (pinfunction "RCK_12") (pintype "input"))
      (node (ref "U28") (pin "12") (pinfunction "RCK_12") (pintype "input"))
      (node (ref "U29") (pin "12") (pinfunction "RCK_12") (pintype "input"))
      (node (ref "U30") (pin "12") (pinfunction "RCK_12") (pintype "input"))
      (node (ref "U31") (pin "12") (pinfunction "RCK_12") (pintype "input"))
    )
    (net (code "341") (name "Net-(U12B-O)") (class "Default")
      (node (ref "U12") (pin "6") (pinfunction "O_6") (pintype "output"))
      (node (ref "U6") (pin "5") (pinfunction "I_5") (pintype "input"))
    )
    (net (code "342") (name "Net-(U13A-1Q)") (class "Default")
      (node (ref "U13") (pin "19") (pinfunction "1Q_19") (pintype "tri_state"))
      (node (ref "U14") (pin "1") (pinfunction "A_1") (pintype "input"))
    )
    (net (code "343") (name "Net-(U13A-2Q)") (class "Default")
      (node (ref "U13") (pin "18") (pinfunction "2Q_18") (pintype "tri_state"))
      (node (ref "U14") (pin "2") (pinfunction "B_2") (pintype "input"))
    )
    (net (code "344") (name "Net-(U13A-C)") (class "Default")
      (node (ref "U13") (pin "11") (pinfunction "C_11") (pintype "input"))
      (node (ref "U6") (pin "6") (pinfunction "O_6") (pintype "output"))
    )
    (net (code "345") (name "Net-(U15A-QH*)") (class "Default")
      (node (ref "U15") (pin "9") (pinfunction "QH*_9") (pintype "tri_state"))
      (node (ref "U16") (pin "14") (pinfunction "SER_14") (pintype "input"))
    )
    (net (code "346") (name "Net-(U16A-QH*)") (class "Default")
      (node (ref "U16") (pin "9") (pinfunction "QH*_9") (pintype "tri_state"))
      (node (ref "U17") (pin "14") (pinfunction "SER_14") (pintype "input"))
    )
    (net (code "347") (name "Net-(U17A-QH*)") (class "Default")
      (node (ref "U17") (pin "9") (pinfunction "QH*_9") (pintype "tri_state"))
      (node (ref "U18") (pin "14") (pinfunction "SER_14") (pintype "input"))
    )
    (net (code "348") (name "Net-(U18A-QH*)") (class "Default")
      (node (ref "U18") (pin "9") (pinfunction "QH*_9") (pintype "tri_state"))
      (node (ref "U19") (pin "14") (pinfunction "SER_14") (pintype "input"))
    )
    (net (code "349") (name "Net-(U19A-QH*)") (class "Default")
      (node (ref "U19") (pin "9") (pinfunction "QH*_9") (pintype "tri_state"))
      (node (ref "U20") (pin "14") (pinfunction "SER_14") (pintype "input"))
    )
    (net (code "350") (name "Net-(U20A-QH*)") (class "Default")
      (node (ref "U20") (pin "9") (pinfunction "QH*_9") (pintype "tri_state"))
      (node (ref "U21") (pin "14") (pinfunction "SER_14") (pintype "input"))
    )
    (net (code "351") (name "Net-(U21A-QH*)") (class "Default")
      (node (ref "U21") (pin "9") (pinfunction "QH*_9") (pintype "tri_state"))
      (node (ref "U22") (pin "14") (pinfunction "SER_14") (pintype "input"))
    )
    (net (code "352") (name "Net-(U22A-QH*)") (class "Default")
      (node (ref "U22") (pin "9") (pinfunction "QH*_9") (pintype "tri_state"))
      (node (ref "U23") (pin "14") (pinfunction "SER_14") (pintype "input"))
    )
    (net (code "353") (name "Net-(U23A-QH*)") (class "Default")
      (node (ref "U23") (pin "9") (pinfunction "QH*_9") (pintype "tri_state"))
      (node (ref "U24") (pin "14") (pinfunction "SER_14") (pintype "input"))
    )
    (net (code "354") (name "Net-(U24A-QH*)") (class "Default")
      (node (ref "U24") (pin "9") (pinfunction "QH*_9") (pintype "tri_state"))
      (node (ref "U25") (pin "14") (pinfunction "SER_14") (pintype "input"))
    )
    (net (code "355") (name "Net-(U25A-QH*)") (class "Default")
      (node (ref "U25") (pin "9") (pinfunction "QH*_9") (pintype "tri_state"))
      (node (ref "U26") (pin "14") (pinfunction "SER_14") (pintype "input"))
    )
    (net (code "356") (name "Net-(U26A-QH*)") (class "Default")
      (node (ref "U26") (pin "9") (pinfunction "QH*_9") (pintype "tri_state"))
      (node (ref "U27") (pin "14") (pinfunction "SER_14") (pintype "input"))
    )
    (net (code "357") (name "Net-(U27A-QH*)") (class "Default")
      (node (ref "U27") (pin "9") (pinfunction "QH*_9") (pintype "tri_state"))
      (node (ref "U28") (pin "14") (pinfunction "SER_14") (pintype "input"))
    )
    (net (code "358") (name "Net-(U28A-QH*)") (class "Default")
      (node (ref "U28") (pin "9") (pinfunction "QH*_9") (pintype "tri_state"))
      (node (ref "U29") (pin "14") (pinfunction "SER_14") (pintype "input"))
    )
    (net (code "359") (name "Net-(U29A-QH*)") (class "Default")
      (node (ref "U29") (pin "9") (pinfunction "QH*_9") (pintype "tri_state"))
      (node (ref "U30") (pin "14") (pinfunction "SER_14") (pintype "input"))
    )
    (net (code "360") (name "Net-(U30A-QH*)") (class "Default")
      (node (ref "U30") (pin "9") (pinfunction "QH*_9") (pintype "tri_state"))
      (node (ref "U31") (pin "14") (pinfunction "SER_14") (pintype "input"))
    )
    (net (code "361") (name "unconnected-(BUSG-S-Pad15)") (class "Default")
      (node (ref "BUS") (pin "15") (pinfunction "S_15") (pintype "passive"))
    )
    (net (code "362") (name "unconnected-(BUSH-S-Pad16)") (class "Default")
      (node (ref "BUS") (pin "16") (pinfunction "S_16") (pintype "passive"))
    )
    (net (code "363") (name "unconnected-(BUSI-S-Pad17)") (class "Default")
      (node (ref "BUS") (pin "17") (pinfunction "S_17") (pintype "passive"))
    )
    (net (code "364") (name "unconnected-(BUSJ-S-Pad18)") (class "Default")
      (node (ref "BUS") (pin "18") (pinfunction "S_18") (pintype "passive"))
    )
    (net (code "365") (name "unconnected-(BUSK-S-Pad19)") (class "Default")
      (node (ref "BUS") (pin "19") (pinfunction "S_19") (pintype "passive"))
    )
    (net (code "366") (name "unconnected-(BUSM-S-Pad20)") (class "Default")
      (node (ref "BUS") (pin "20") (pinfunction "S_20") (pintype "passive"))
    )
    (net (code "367") (name "unconnected-(BUSN-S-Pad21)") (class "Default")
      (node (ref "BUS") (pin "21") (pinfunction "S_21") (pintype "passive"))
    )
    (net (code "368") (name "unconnected-(BUSO-S-Pad22)") (class "Default")
      (node (ref "BUS") (pin "22") (pinfunction "S_22") (pintype "passive"))
    )
    (net (code "369") (name "unconnected-(SV3I-S-Pad17)") (class "Default")
      (node (ref "SV3") (pin "17") (pinfunction "S_17") (pintype "passive"))
    )
    (net (code "370") (name "unconnected-(SV3J-S-Pad18)") (class "Default")
      (node (ref "SV3") (pin "18") (pinfunction "S_18") (pintype "passive"))
    )
    (net (code "371") (name "unconnected-(SV3K-S-Pad19)") (class "Default")
      (node (ref "SV3") (pin "19") (pinfunction "S_19") (pintype "passive"))
    )
    (net (code "372") (name "unconnected-(SV3M-S-Pad20)") (class "Default")
      (node (ref "SV3") (pin "20") (pinfunction "S_20") (pintype "passive"))
    )
    (net (code "373") (name "unconnected-(SV3N-S-Pad21)") (class "Default")
      (node (ref "SV3") (pin "21") (pinfunction "S_21") (pintype "passive"))
    )
    (net (code "374") (name "unconnected-(SV3O-S-Pad22)") (class "Default")
      (node (ref "SV3") (pin "22") (pinfunction "S_22") (pintype "passive"))
    )
    (net (code "375") (name "unconnected-(SV3P-S-Pad23)") (class "Default")
      (node (ref "SV3") (pin "23") (pinfunction "S_23") (pintype "passive"))
    )
    (net (code "376") (name "unconnected-(SV3Q-S-Pad24)") (class "Default")
      (node (ref "SV3") (pin "24") (pinfunction "S_24") (pintype "passive"))
    )
    (net (code "377") (name "unconnected-(SV4AA-S-Pad33)") (class "Default")
      (node (ref "SV4") (pin "33") (pinfunction "S_33") (pintype "passive"))
    )
    (net (code "378") (name "unconnected-(SV4R-S-Pad25)") (class "Default")
      (node (ref "SV4") (pin "25") (pinfunction "S_25") (pintype "passive"))
    )
    (net (code "379") (name "unconnected-(SV4S-S-Pad26)") (class "Default")
      (node (ref "SV4") (pin "26") (pinfunction "S_26") (pintype "passive"))
    )
    (net (code "380") (name "unconnected-(SV4T-S-Pad27)") (class "Default")
      (node (ref "SV4") (pin "27") (pinfunction "S_27") (pintype "passive"))
    )
    (net (code "381") (name "unconnected-(SV4U-S-Pad28)") (class "Default")
      (node (ref "SV4") (pin "28") (pinfunction "S_28") (pintype "passive"))
    )
    (net (code "382") (name "unconnected-(SV4V-S-Pad29)") (class "Default")
      (node (ref "SV4") (pin "29") (pinfunction "S_29") (pintype "passive"))
    )
    (net (code "383") (name "unconnected-(SV4X-S-Pad30)") (class "Default")
      (node (ref "SV4") (pin "30") (pinfunction "S_30") (pintype "passive"))
    )
    (net (code "384") (name "unconnected-(SV4Y-S-Pad31)") (class "Default")
      (node (ref "SV4") (pin "31") (pinfunction "S_31") (pintype "passive"))
    )
    (net (code "385") (name "unconnected-(SV4Z-S-Pad32)") (class "Default")
      (node (ref "SV4") (pin "32") (pinfunction "S_32") (pintype "passive"))
    )
    (net (code "386") (name "unconnected-(U3A-B1-Pad18)") (class "Default")
      (node (ref "U3") (pin "18") (pinfunction "B1_18") (pintype "bidirectional"))
    )
    (net (code "387") (name "unconnected-(U3A-B2-Pad17)") (class "Default")
      (node (ref "U3") (pin "17") (pinfunction "B2_17") (pintype "bidirectional"))
    )
    (net (code "388") (name "unconnected-(U3A-B4-Pad15)") (class "Default")
      (node (ref "U3") (pin "15") (pinfunction "B4_15") (pintype "bidirectional"))
    )
    (net (code "389") (name "unconnected-(U3A-B6-Pad13)") (class "Default")
      (node (ref "U3") (pin "13") (pinfunction "B6_13") (pintype "bidirectional"))
    )
    (net (code "390") (name "unconnected-(U6E-O-Pad10)") (class "Default")
      (node (ref "U6") (pin "10") (pinfunction "O_10") (pintype "output"))
    )
    (net (code "391") (name "unconnected-(U6F-O-Pad12)") (class "Default")
      (node (ref "U6") (pin "12") (pinfunction "O_12") (pintype "output"))
    )
    (net (code "392") (name "unconnected-(U7B-Q-Pad9)") (class "Default")
      (node (ref "U7") (pin "9") (pinfunction "Q_9") (pintype "output"))
    )
    (net (code "393") (name "unconnected-(U7B-~{Q}-Pad8)") (class "Default")
      (node (ref "U7") (pin "8") (pinfunction "~{Q}_8") (pintype "output"))
    )
    (net (code "394") (name "unconnected-(U9A-QA-Pad3)") (class "Default")
      (node (ref "U9") (pin "3") (pinfunction "QA_3") (pintype "output"))
    )
    (net (code "395") (name "unconnected-(U9A-QB-Pad4)") (class "Default")
      (node (ref "U9") (pin "4") (pinfunction "QB_4") (pintype "output"))
    )
    (net (code "396") (name "unconnected-(U9A-QC-Pad5)") (class "Default")
      (node (ref "U9") (pin "5") (pinfunction "QC_5") (pintype "output"))
    )
    (net (code "397") (name "unconnected-(U9B-QA-Pad11)") (class "Default")
      (node (ref "U9") (pin "11") (pinfunction "QA_11") (pintype "output"))
    )
    (net (code "398") (name "unconnected-(U9B-QB-Pad10)") (class "Default")
      (node (ref "U9") (pin "10") (pinfunction "QB_10") (pintype "output"))
    )
    (net (code "399") (name "unconnected-(U9B-QC-Pad9)") (class "Default")
      (node (ref "U9") (pin "9") (pinfunction "QC_9") (pintype "output"))
    )
    (net (code "400") (name "unconnected-(U9B-QD-Pad8)") (class "Default")
      (node (ref "U9") (pin "8") (pinfunction "QD_8") (pintype "output"))
    )
    (net (code "401") (name "unconnected-(U10C-O-Pad8)") (class "Default")
      (node (ref "U10") (pin "8") (pinfunction "O_8") (pintype "output"))
    )
    (net (code "402") (name "unconnected-(U10D-O-Pad11)") (class "Default")
      (node (ref "U10") (pin "11") (pinfunction "O_11") (pintype "output"))
    )
    (net (code "403") (name "unconnected-(U12C-O-Pad8)") (class "Default")
      (node (ref "U12") (pin "8") (pinfunction "O_8") (pintype "output"))
    )
    (net (code "404") (name "unconnected-(U12D-O-Pad11)") (class "Default")
      (node (ref "U12") (pin "11") (pinfunction "O_11") (pintype "output"))
    )
    (net (code "405") (name "unconnected-(U13A-3Q-Pad17)") (class "Default")
      (node (ref "U13") (pin "17") (pinfunction "3Q_17") (pintype "tri_state"))
    )
    (net (code "406") (name "unconnected-(U13A-4Q-Pad16)") (class "Default")
      (node (ref "U13") (pin "16") (pinfunction "4Q_16") (pintype "tri_state"))
    )
    (net (code "407") (name "unconnected-(U13A-5Q-Pad15)") (class "Default")
      (node (ref "U13") (pin "15") (pinfunction "5Q_15") (pintype "tri_state"))
    )
    (net (code "408") (name "unconnected-(U13A-6Q-Pad14)") (class "Default")
      (node (ref "U13") (pin "14") (pinfunction "6Q_14") (pintype "tri_state"))
    )
    (net (code "409") (name "unconnected-(U13A-7Q-Pad13)") (class "Default")
      (node (ref "U13") (pin "13") (pinfunction "7Q_13") (pintype "tri_state"))
    )
    (net (code "410") (name "unconnected-(U13A-8Q-Pad12)") (class "Default")
      (node (ref "U13") (pin "12") (pinfunction "8Q_12") (pintype "tri_state"))
    )
    (net (code "411") (name "unconnected-(U14A-Y0-Pad15)") (class "Default")
      (node (ref "U14") (pin "15") (pinfunction "Y0_15") (pintype "output"))
    )
    (net (code "412") (name "unconnected-(U14A-Y4-Pad11)") (class "Default")
      (node (ref "U14") (pin "11") (pinfunction "Y4_11") (pintype "output"))
    )
    (net (code "413") (name "unconnected-(U14A-Y5-Pad10)") (class "Default")
      (node (ref "U14") (pin "10") (pinfunction "Y5_10") (pintype "output"))
    )
    (net (code "414") (name "unconnected-(U14A-Y6-Pad9)") (class "Default")
      (node (ref "U14") (pin "9") (pinfunction "Y6_9") (pintype "output"))
    )
    (net (code "415") (name "unconnected-(U14A-Y7-Pad7)") (class "Default")
      (node (ref "U14") (pin "7") (pinfunction "Y7_7") (pintype "output"))
    )
    (net (code "416") (name "unconnected-(U31A-QH*-Pad9)") (class "Default")
      (node (ref "U31") (pin "9") (pinfunction "QH*_9") (pintype "tri_state"))
    )
  )
)
